# Sheet1.net
KiCad netlist of a schematic drawn in Altium Designer
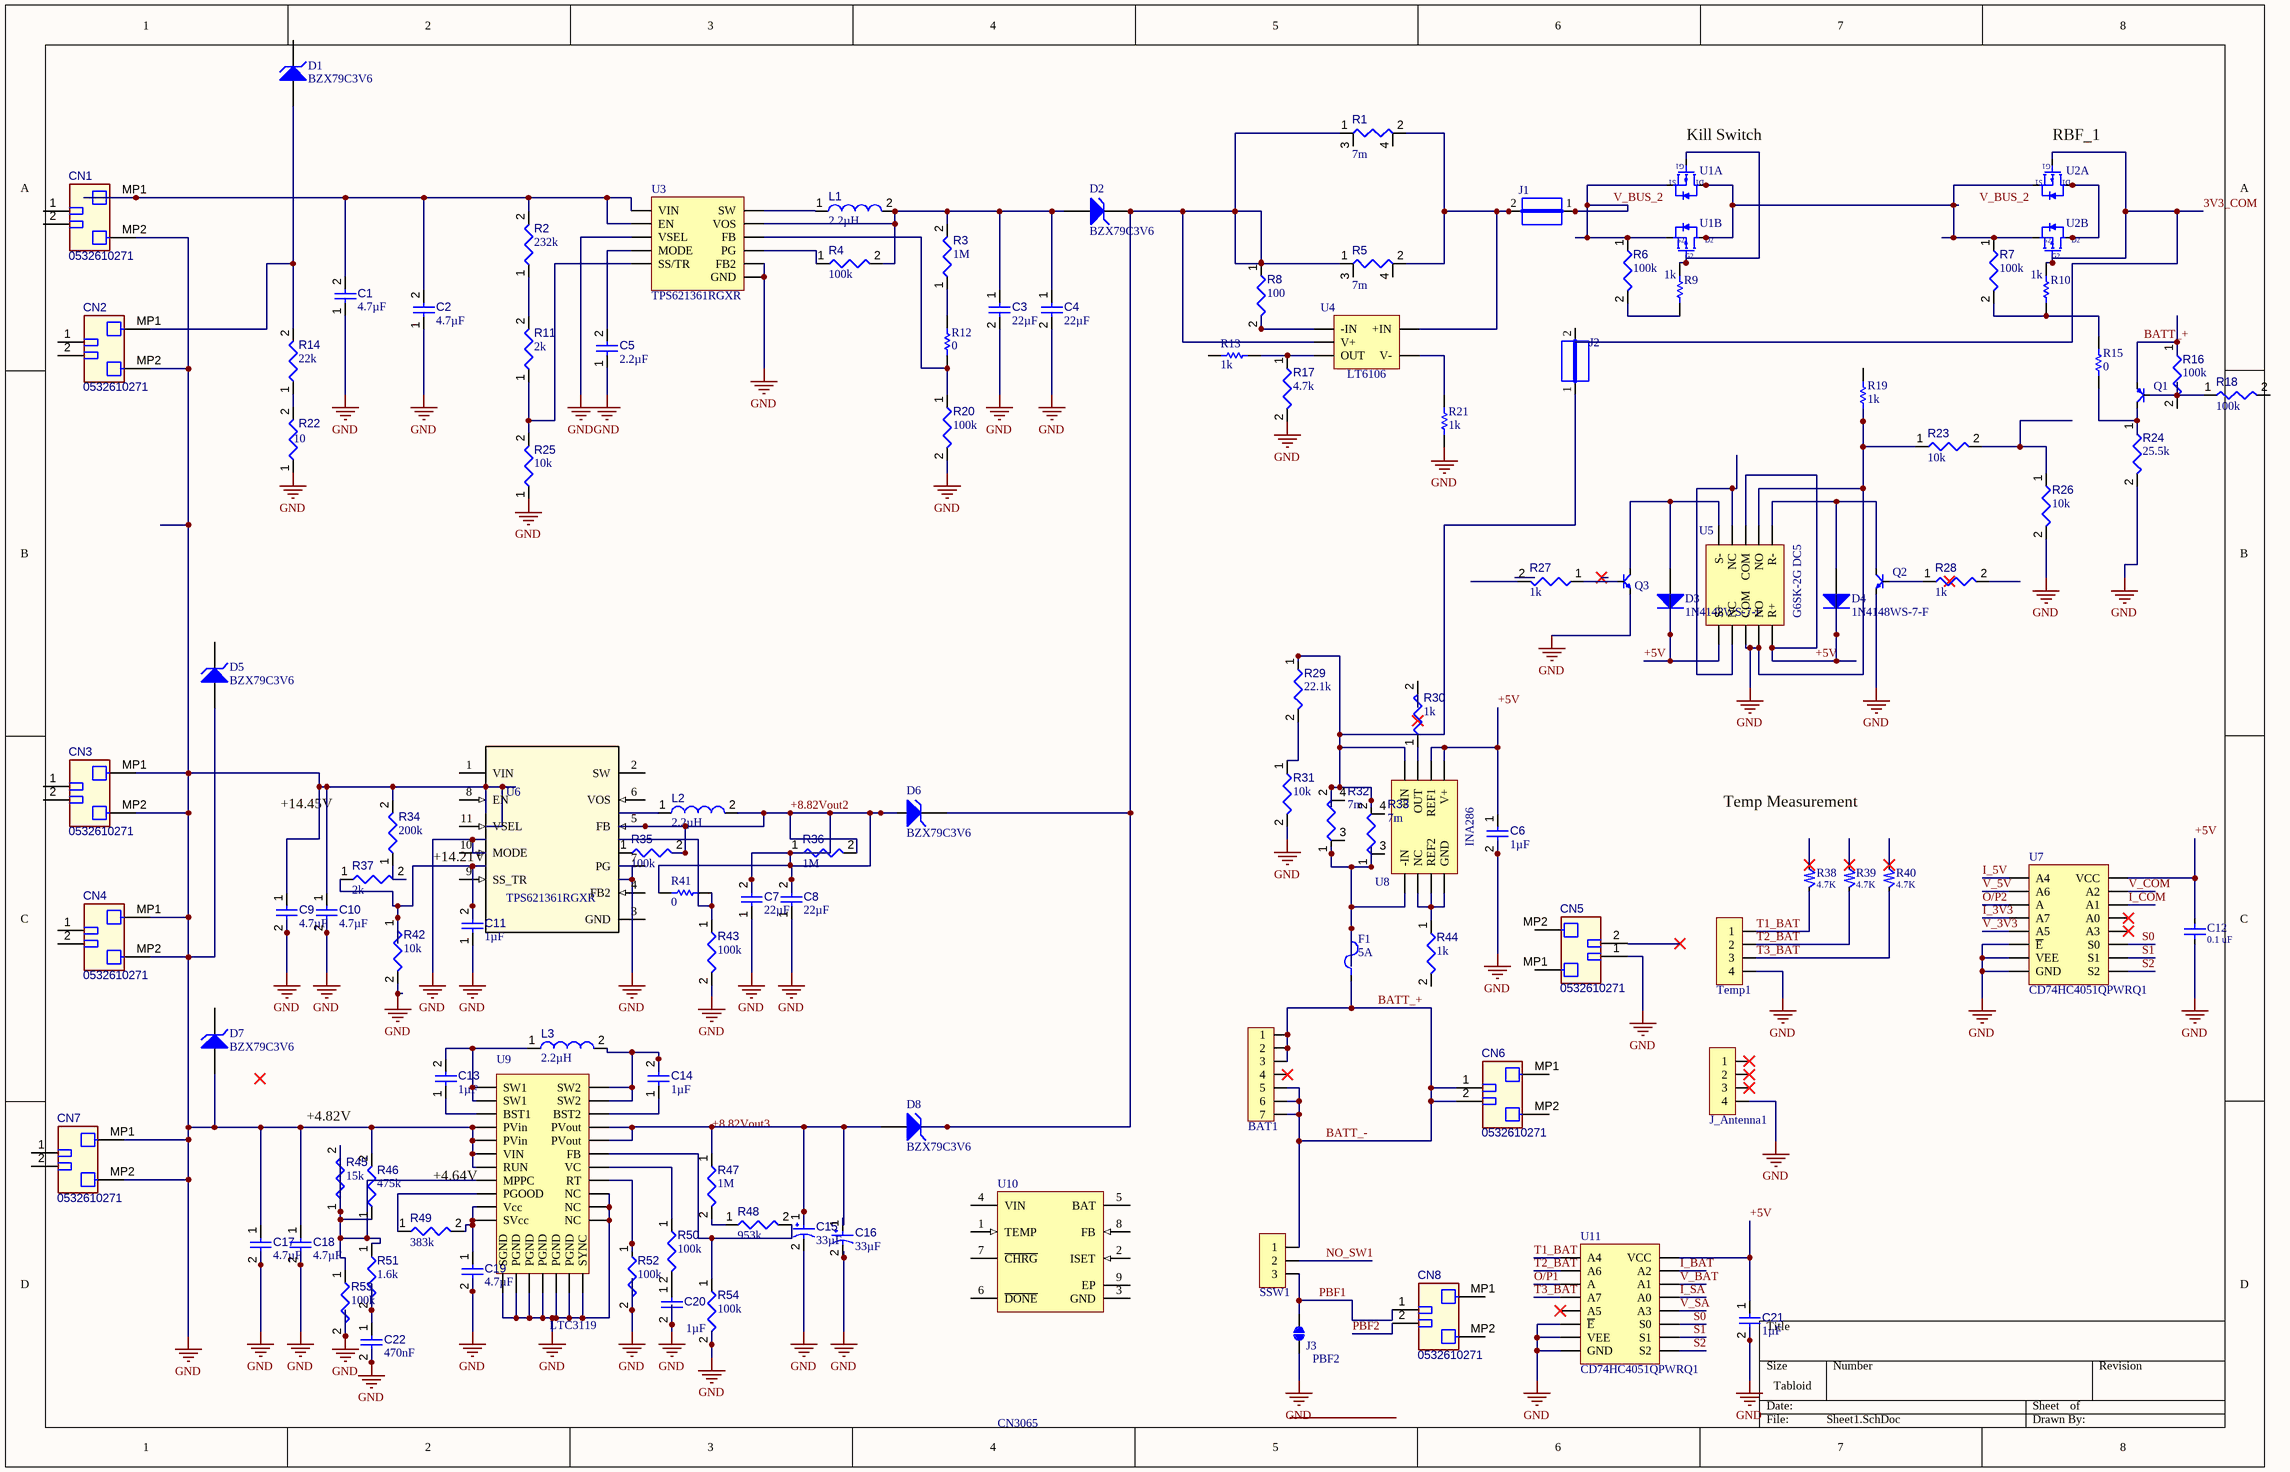
[diagram p0: Sheet1.SchDoc]

(export (version "E")
  (design (tool "Eeschema 10.0.6"))
  (components
    (comp (ref "BAT1")
      (value "53261-0771")
      (footprint "Molex_0_MFG")
      (description "CONN HEADER SMD R/A 7POS 1.25MM")
      (fields (field (name "MANUFACTURER") "Molex"))
      (libsource (lib "All_N_Cube3_Components") (part "53261-0771"))
    )
    (comp (ref "C1")
      (value "4.7µF")
      (footprint "CAPC0603(1608)100_L")
      (description "Chip Capacitor, 4.7µF +/-20%, 10V, 0603, Thickness 1 mm")
      (fields (field (name "TOLERANCE") "10%") (field (name "Comment") "Capacitor 4.7µF +/-20% 10V 0603"))
      (libsource (lib "Meshack Kinyua") (part "CAP-NP-2"))
    )
    (comp (ref "C2")
      (value "4.7µF")
      (footprint "CAPC0603(1608)100_L")
      (description "Chip Capacitor, 4.7µF +/-20%, 10V, 0603, Thickness 1 mm")
      (fields (field (name "TOLERANCE") "10%") (field (name "Comment") "Capacitor 4.7µF +/-20% 10V 0603"))
      (libsource (lib "Meshack Kinyua") (part "CAP-NP-2"))
    )
    (comp (ref "C3")
      (value "22µF")
      (footprint "CAPC0805(2012)145_L")
      (description "Chip Capacitor, 22µF +/-40%, 16V, 0805, Thickness 1.45 mm")
      (fields (field (name "TOLERANCE") "5%") (field (name "Comment") "Capacitor 22µF +/-40% 16V 0805"))
      (libsource (lib "Meshack Kinyua") (part "CAP-NP-2"))
    )
    (comp (ref "C4")
      (value "22µF")
      (footprint "CAPC0805(2012)145_L")
      (description "Chip Capacitor, 22µF +/-40%, 16V, 0805, Thickness 1.45 mm")
      (fields (field (name "TOLERANCE") "5%") (field (name "Comment") "Capacitor 22µF +/-40% 16V 0805"))
      (libsource (lib "Meshack Kinyua") (part "CAP-NP-2"))
    )
    (comp (ref "C5")
      (value "2.2µF")
      (footprint "CAPC0402(1005)60_L")
      (description "Chip Capacitor, 2,2µF +/-20%, 10V, 0402, Thickness 0.6 mm")
      (fields (field (name "TOLERANCE") "10%") (field (name "Comment") "Capacitor 2,2µF +/-20% 10V 0402"))
      (libsource (lib "Meshack Kinyua") (part "CAP-NP-2"))
    )
    (comp (ref "C6")
      (value "1µF")
      (footprint "CAPC1608X90X40LL10T20")
      (description "Chip Capacitor, 1 uF, +/- 10%, 25 V, 0603 (1608 Metric)")
      (fields (field (name "TOLERANCE") "10%") (field (name "Comment") "Capacitor 1 uF +/- 10% 25 V 0603"))
      (libsource (lib "Meshack Kinyua") (part "CAP-NP-2"))
    )
    (comp (ref "C7")
      (value "22µF")
      (footprint "CAPC0805(2012)145_L")
      (description "Chip Capacitor, 22µF +/-40%, 16V, 0805, Thickness 1.45 mm")
      (fields (field (name "TOLERANCE") "5%") (field (name "Comment") "Capacitor 22µF +/-40% 16V 0805"))
      (libsource (lib "Meshack Kinyua") (part "CAP-NP-2"))
    )
    (comp (ref "C8")
      (value "22µF")
      (footprint "CAPC0805(2012)145_L")
      (description "Chip Capacitor, 22µF +/-40%, 16V, 0805, Thickness 1.45 mm")
      (fields (field (name "TOLERANCE") "5%") (field (name "Comment") "Capacitor 22µF +/-40% 16V 0805"))
      (libsource (lib "Meshack Kinyua") (part "CAP-NP-2"))
    )
    (comp (ref "C9")
      (value "4.7µF")
      (footprint "CAPC0603(1608)100_L")
      (description "Chip Capacitor, 4.7µF +/-20%, 10V, 0603, Thickness 1 mm")
      (fields (field (name "TOLERANCE") "10%") (field (name "Comment") "Capacitor 4.7µF +/-20% 10V 0603"))
      (libsource (lib "Meshack Kinyua") (part "CAP-NP-2"))
    )
    (comp (ref "C10")
      (value "4.7µF")
      (footprint "CAPC0603(1608)100_L")
      (description "Chip Capacitor, 4.7µF +/-20%, 10V, 0603, Thickness 1 mm")
      (fields (field (name "TOLERANCE") "10%") (field (name "Comment") "Capacitor 4.7µF +/-20% 10V 0603"))
      (libsource (lib "Meshack Kinyua") (part "CAP-NP-2"))
    )
    (comp (ref "C11")
      (value "1µF")
      (footprint "CAPC1608X94X35NL15T15")
      (description "Chip Capacitor, 1 uF, +/- 10%, 16 V, 0603 (1608 Metric)")
      (fields (field (name "TOLERANCE") "10%") (field (name "Comment") "Capacitor 1 uF +/- 10% 16 V 0603"))
      (libsource (lib "Meshack Kinyua") (part "CAP-NP-2"))
    )
    (comp (ref "C12")
      (value "0.1 uF")
      (footprint "C0805C104J4RACTU")
      (description "CAP CER 0.1UF 16V X7R 0805")
      (fields
        (field (name "MANUFACTURER") "KEMET")
        (field (name "MANUFACTURER PART NUMBER") "C0805C104J4RACTU")
      )
      (libsource (lib "All_N_Cube3_Components") (part "C0805C104J4RACTU"))
    )
    (comp (ref "C13")
      (value "1µF")
      (footprint "CAPC1608X94X35NL15T15")
      (description "Chip Capacitor, 1 uF, +/- 10%, 16 V, 0603 (1608 Metric)")
      (fields (field (name "TOLERANCE") "10%") (field (name "Comment") "Capacitor 1 uF +/- 10% 16 V 0603"))
      (libsource (lib "Meshack Kinyua") (part "CAP-NP-2"))
    )
    (comp (ref "C14")
      (value "1µF")
      (footprint "CAPC1608X94X35NL15T15")
      (description "Chip Capacitor, 1 uF, +/- 10%, 16 V, 0603 (1608 Metric)")
      (fields (field (name "TOLERANCE") "10%") (field (name "Comment") "Capacitor 1 uF +/- 10% 16 V 0603"))
      (libsource (lib "Meshack Kinyua") (part "CAP-NP-2"))
    )
    (comp (ref "C15")
      (value "33µF")
      (footprint "EEF-CX1E330R-Footprint-1")
      (description "Aluminum Organic Polymer Capacitors 33uF 25volt SP-Cap AEC-Q200")
      (fields (field (name "TOLERANCE") "20%") (field (name "Comment") "Capacitor 33µF +/-20% 25V 2917"))
      (libsource (lib "Meshack Kinyua") (part "CAP-P-2"))
    )
    (comp (ref "C16")
      (value "33µF")
      (footprint "EEF-CX1E330R-Footprint-1")
      (description "Aluminum Organic Polymer Capacitors 33uF 25volt SP-Cap AEC-Q200")
      (fields (field (name "TOLERANCE") "20%") (field (name "Comment") "Capacitor 33µF +/-20% 25V 2917"))
      (libsource (lib "Meshack Kinyua") (part "CAP-P-2"))
    )
    (comp (ref "C17")
      (value "4.7µF")
      (footprint "CAPC0603(1608)100_L")
      (description "Chip Capacitor, 4.7µF +/-20%, 10V, 0603, Thickness 1 mm")
      (fields (field (name "TOLERANCE") "10%") (field (name "Comment") "Capacitor 4.7µF +/-20% 10V 0603"))
      (libsource (lib "Meshack Kinyua") (part "CAP-NP-2"))
    )
    (comp (ref "C18")
      (value "4.7µF")
      (footprint "CAPC0603(1608)100_L")
      (description "Chip Capacitor, 4.7µF +/-20%, 10V, 0603, Thickness 1 mm")
      (fields (field (name "TOLERANCE") "10%") (field (name "Comment") "Capacitor 4.7µF +/-20% 10V 0603"))
      (libsource (lib "Meshack Kinyua") (part "CAP-NP-2"))
    )
    (comp (ref "C19")
      (value "4.7µF")
      (footprint "CAPC0603(1608)100_L")
      (description "Chip Capacitor, 4.7µF +/-20%, 10V, 0603, Thickness 1 mm")
      (fields (field (name "TOLERANCE") "10%") (field (name "Comment") "Capacitor 4.7µF +/-20% 10V 0603"))
      (libsource (lib "Meshack Kinyua") (part "CAP-NP-2"))
    )
    (comp (ref "C20")
      (value "1µF")
      (footprint "CAPC1005X55X25LL05T10")
      (description "Chip Capacitor, 1 uF, +/- 10%, 6.3 V, 0402 (1005 Metric)")
      (fields (field (name "TOLERANCE") "10%") (field (name "Comment") "Capacitor 1 uF +/- 10% 6.3 V 0402"))
      (libsource (lib "Meshack Kinyua") (part "CAP-NP-2"))
    )
    (comp (ref "C21")
      (value "1µF")
      (footprint "CAPC1608X94X35NL15T15")
      (description "Chip Capacitor, 1 uF, +/- 10%, 16 V, 0603 (1608 Metric)")
      (fields (field (name "TOLERANCE") "10%") (field (name "Comment") "Capacitor 1 uF +/- 10% 16 V 0603"))
      (libsource (lib "Meshack Kinyua") (part "CAP-NP-2"))
    )
    (comp (ref "C22")
      (value "470nF")
      (footprint "CAPC0402(1005)60_L")
      (description "Chip Capacitor, 470nF +/-40%, 10V, 0402, Thickness 0.6 mm")
      (fields (field (name "TOLERANCE") "20%") (field (name "Comment") "Capacitor 470nF +/-40% 10V 0402"))
      (libsource (lib "Meshack Kinyua") (part "CAP-NP-2"))
    )
    (comp (ref "CN1")
      (value "0532610271")
      (footprint "MOLX-532610271_V")
      (description "Header, Pitch 1.25 mm, 1 x 2 Position, Height 3.6 mm, -40 to 85 degC")
      (libsource (lib "Meshack Kinyua") (part "CMP-00144-3"))
    )
    (comp (ref "CN2")
      (value "0532610271")
      (footprint "MOLX-532610271_V")
      (description "Header, Pitch 1.25 mm, 1 x 2 Position, Height 3.6 mm, -40 to 85 degC")
      (libsource (lib "Meshack Kinyua") (part "CMP-00144-3"))
    )
    (comp (ref "CN3")
      (value "0532610271")
      (footprint "MOLX-532610271_V")
      (description "Header, Pitch 1.25 mm, 1 x 2 Position, Height 3.6 mm, -40 to 85 degC")
      (libsource (lib "Meshack Kinyua") (part "CMP-00144-3"))
    )
    (comp (ref "CN4")
      (value "0532610271")
      (footprint "MOLX-532610271_V")
      (description "Header, Pitch 1.25 mm, 1 x 2 Position, Height 3.6 mm, -40 to 85 degC")
      (libsource (lib "Meshack Kinyua") (part "CMP-00144-3"))
    )
    (comp (ref "CN5")
      (value "0532610271")
      (footprint "MOLX-532610271_V")
      (description "Header, Pitch 1.25 mm, 1 x 2 Position, Height 3.6 mm, -40 to 85 degC")
      (libsource (lib "") (part "CMP-00144-3_1"))
    )
    (comp (ref "CN6")
      (value "0532610271")
      (footprint "MOLX-532610271_V")
      (description "Header, Pitch 1.25 mm, 1 x 2 Position, Height 3.6 mm, -40 to 85 degC")
      (libsource (lib "Meshack Kinyua") (part "CMP-00144-3"))
    )
    (comp (ref "CN7")
      (value "0532610271")
      (footprint "MOLX-532610271_V")
      (description "Header, Pitch 1.25 mm, 1 x 2 Position, Height 3.6 mm, -40 to 85 degC")
      (libsource (lib "Meshack Kinyua") (part "CMP-00144-3"))
    )
    (comp (ref "CN8")
      (value "0532610271")
      (footprint "MOLX-532610271_V")
      (description "Header, Pitch 1.25 mm, 1 x 2 Position, Height 3.6 mm, -40 to 85 degC")
      (libsource (lib "Meshack Kinyua") (part "CMP-00144-3"))
    )
    (comp (ref "D1")
      (value "BZX79C3V6")
      (footprint "FAIR-DO-35-2")
      (description "Zener Diode, 3.6 V, 5 mA, -65 to 200 degC, 2-Pin DO-35, RoHS, Bulk")
      (fields (field (name "MANUFACTURER") "Fairchild Semiconductor") (field (name "TOLERANCE") "6%"))
      (libsource (lib "Meshack Kinyua") (part "DZEN-AK-2"))
    )
    (comp (ref "D2")
      (value "BZX79C3V6")
      (footprint "FAIR-DO-35-2")
      (description "Zener Diode, 3.6 V, 5 mA, -65 to 200 degC, 2-Pin DO-35, RoHS, Bulk")
      (fields (field (name "MANUFACTURER") "Fairchild Semiconductor") (field (name "TOLERANCE") "6%"))
      (libsource (lib "Meshack Kinyua") (part "DZEN-AK-2"))
    )
    (comp (ref "D3")
      (value "1N4148WS-7-F")
      (footprint "DIOD-SOD323-2-A_V")
      (description "Fast Switching Diode, 75 V, 0.3 A, -65 to 150 degC, 2-Pin SOD323, RoHS, Tape and Reel")
      (fields (field (name "MANUFACTURER") "Diodes Inc"))
      (libsource (lib "Meshack Kinyua") (part "D-AK-2"))
    )
    (comp (ref "D4")
      (value "1N4148WS-7-F")
      (footprint "DIOD-SOD323-2-A_V")
      (description "Fast Switching Diode, 75 V, 0.3 A, -65 to 150 degC, 2-Pin SOD323, RoHS, Tape and Reel")
      (fields (field (name "MANUFACTURER") "Diodes Inc"))
      (libsource (lib "Meshack Kinyua") (part "D-AK-2"))
    )
    (comp (ref "D5")
      (value "BZX79C3V6")
      (footprint "FAIR-DO-35-2")
      (description "Zener Diode, 3.6 V, 5 mA, -65 to 200 degC, 2-Pin DO-35, RoHS, Bulk")
      (fields (field (name "MANUFACTURER") "Fairchild Semiconductor") (field (name "TOLERANCE") "6%"))
      (libsource (lib "Meshack Kinyua") (part "DZEN-AK-2"))
    )
    (comp (ref "D6")
      (value "BZX79C3V6")
      (footprint "FAIR-DO-35-2")
      (description "Zener Diode, 3.6 V, 5 mA, -65 to 200 degC, 2-Pin DO-35, RoHS, Bulk")
      (fields (field (name "MANUFACTURER") "Fairchild Semiconductor") (field (name "TOLERANCE") "6%"))
      (libsource (lib "Meshack Kinyua") (part "DZEN-AK-2"))
    )
    (comp (ref "D7")
      (value "BZX79C3V6")
      (footprint "FAIR-DO-35-2")
      (description "Zener Diode, 3.6 V, 5 mA, -65 to 200 degC, 2-Pin DO-35, RoHS, Bulk")
      (fields (field (name "MANUFACTURER") "Fairchild Semiconductor") (field (name "TOLERANCE") "6%"))
      (libsource (lib "Meshack Kinyua") (part "DZEN-AK-2"))
    )
    (comp (ref "D8")
      (value "BZX79C3V6")
      (footprint "FAIR-DO-35-2")
      (description "Zener Diode, 3.6 V, 5 mA, -65 to 200 degC, 2-Pin DO-35, RoHS, Bulk")
      (fields (field (name "MANUFACTURER") "Fairchild Semiconductor") (field (name "TOLERANCE") "6%"))
      (libsource (lib "Meshack Kinyua") (part "DZEN-AK-2"))
    )
    (comp (ref "F1")
      (value "1206L500/12SLPR")
      (footprint "1206L500/12SLPR")
      (description "PTC RESET FUSE 5.0A 12V 1206")
      (fields (field (name "MANUFACTURER") "Littelfuse") (field (name "TRIP CURRENT") "5A"))
      (libsource (lib "All_N_Cube3_Components") (part "1206L500/12SLPR"))
    )
    (comp (ref "J1") (value "JUMPER") (footprint "JUMPER") (libsource (lib "Meshack Kinyua") (part "JUMPER")))
    (comp (ref "J2") (value "JUMPER") (footprint "JUMPER") (libsource (lib "") (part "JUMPER_1")))
    (comp (ref "J3")
      (value "JUMPER")
      (footprint "JUMPER")
      (description "OPTION SELECTION 2POS PAD")
      (libsource (lib "RG_Projects") (part "JUMPER"))
    )
    (comp (ref "J_Antenna1")
      (value "53261-0471")
      (footprint "53261-0471")
      (description "CONN HEADER SMD R/A 4POS 1.25MM")
      (fields (field (name "MANUFACTURER") "Molex"))
      (libsource (lib "RG_Projects") (part "53261-0471"))
    )
    (comp (ref "L1")
      (value "2.2µH")
      (footprint "IND1005X55X20VL5T10")
      (description "Chip Inductor, 2.2 nH, +/- 0.3 nH, 400 mA, -40 to 85 degC, 0402 (1005 Metric), RoHS, Tape and Reel")
      (fields (field (name "MANUFACTURER") "Panasonic") (field (name "TOLERANCE") "5%"))
      (libsource (lib "Meshack Kinyua") (part "IND-2"))
    )
    (comp (ref "L2")
      (value "2.2µH")
      (footprint "IND1005X55X20VL5T10")
      (description "Chip Inductor, 2.2 nH, +/- 0.3 nH, 400 mA, -40 to 85 degC, 0402 (1005 Metric), RoHS, Tape and Reel")
      (fields (field (name "MANUFACTURER") "Panasonic") (field (name "TOLERANCE") "5%"))
      (libsource (lib "Meshack Kinyua") (part "IND-2"))
    )
    (comp (ref "L3")
      (value "2.2µH")
      (footprint "IND1005X55X20VL5T10")
      (description "Chip Inductor, 2.2 nH, +/- 0.3 nH, 400 mA, -40 to 85 degC, 0402 (1005 Metric), RoHS, Tape and Reel")
      (fields (field (name "MANUFACTURER") "Panasonic") (field (name "TOLERANCE") "5%"))
      (libsource (lib "Meshack Kinyua") (part "IND-2"))
    )
    (comp (ref "Q1")
      (value "CMPT404A TR")
      (footprint "CMPT404A TR")
      (description "Bipolar Transistors - BJT PNP Silicon Chopper SMT Transistor")
      (fields (field (name "MANUFACTURER") "Central Semiconductor"))
      (libsource (lib "All_N_Cube3_Components") (part "CMPT404A TR"))
    )
    (comp (ref "Q2")
      (value "SMMBT3904LT3G")
      (footprint "SMMBT3904LT3G")
      (description "TRANS NPN 40V 0.2A SOT23")
      (fields (field (name "MANUFACTURER") "ON Semiconductor"))
      (libsource (lib "All_N_Cube3_Components") (part "SMMBT3904LT3G"))
    )
    (comp (ref "Q3")
      (value "SMMBT3904LT3G")
      (footprint "SMMBT3904LT3G")
      (description "TRANS NPN 40V 0.2A SOT23")
      (fields (field (name "MANUFACTURER") "ON Semiconductor"))
      (libsource (lib "All_N_Cube3_Components") (part "SMMBT3904LT3G"))
    )
    (comp (ref "R1")
      (value "7m")
      (footprint "SUSUMU-3216T4A")
      (description "Chip Resistor, 0,007 Ohms, +/-1%, 63 mW, -55 to 155 degC, 1206")
      (fields (field (name "TOLERANCE") "1%") (field (name "Comment") "Resistor 7mR +/-1% 1206 63 mW"))
      (libsource (lib "Meshack Kinyua") (part "RES-4"))
    )
    (comp (ref "R2")
      (value "232k")
      (footprint "RESC0402(1005)_L")
      (description "Chip Resistor, 232 kOhms, +/-1 %, 63 mW, -55 to 155 degC, 0402")
      (fields (field (name "POWER") "63mW") (field (name "TOLERANCE") "1%"))
      (libsource (lib "Meshack Kinyua") (part "RES-2"))
    )
    (comp (ref "R3")
      (value "1M")
      (footprint "RESC0402(1005)_L")
      (description "Chip Resistor, 1 MOhms, +/-5 %, 63 mW, -55 to 155 degC, 0402")
      (fields (field (name "POWER") "63mW") (field (name "TOLERANCE") "5%"))
      (libsource (lib "Meshack Kinyua") (part "RES-2"))
    )
    (comp (ref "R4")
      (value "100k")
      (footprint "RESC3216X60X45ML15T20")
      (description "Chip Resistor, 100 KOhm, +/- 1%, 0.25 W, -55 to 155 degC, 1206 (3216 Metric)")
      (fields (field (name "TOLERANCE") "1%") (field (name "POWER") "250mW"))
      (libsource (lib "Meshack Kinyua") (part "RES-2"))
    )
    (comp (ref "R5")
      (value "7m")
      (footprint "SUSUMU-3216T4A")
      (description "Chip Resistor, 0,007 Ohms, +/-1%, 63 mW, -55 to 155 degC, 1206")
      (fields (field (name "TOLERANCE") "1%") (field (name "Comment") "Resistor 7mR +/-1% 1206 63 mW"))
      (libsource (lib "Meshack Kinyua") (part "RES-4"))
    )
    (comp (ref "R6")
      (value "100k")
      (footprint "RESC1608X55X25ML10T15")
      (description "Chip Resistor, 100 KOhm, +/- 1%, 0.1 W, -55 to 155 degC, 0603 (1608 Metric)")
      (fields (field (name "TOLERANCE") "1%") (field (name "POWER") "100mW"))
      (libsource (lib "Meshack Kinyua") (part "RES-2"))
    )
    (comp (ref "R7")
      (value "100k")
      (footprint "RESC1608X55X25ML10T15")
      (description "Chip Resistor, 100 KOhm, +/- 1%, 0.1 W, -55 to 155 degC, 0603 (1608 Metric)")
      (fields (field (name "TOLERANCE") "1%") (field (name "POWER") "100mW"))
      (libsource (lib "Meshack Kinyua") (part "RES-2"))
    )
    (comp (ref "R8")
      (value "100")
      (footprint "RESA60-630X240")
      (description "Axial Resistor, 100 Ohm, +/- 1%, 0.25 W, -55 to 155 degC, 2-Pin THD, RoHS, Bulk")
      (fields (field (name "MANUFACTURER") "Yageo") (field (name "TOLERANCE") "1%"))
      (libsource (lib "Meshack Kinyua") (part "RES-2"))
    )
    (comp (ref "R9")
      (value "1k")
      (footprint "RESC3116X70X50ML13T20")
      (description "Chip Resistor, 1 KOhm, +/- 1%, 0.25 W, -55 to 155 degC, 1206 (3216 Metric)")
      (fields (field (name "TOLERANCE") "1%") (field (name "POWER") "250mW"))
      (libsource (lib "") (part "RES-2_1"))
    )
    (comp (ref "R10")
      (value "1k")
      (footprint "RESC3116X70X50ML13T20")
      (description "Chip Resistor, 1 KOhm, +/- 1%, 0.25 W, -55 to 155 degC, 1206 (3216 Metric)")
      (fields (field (name "TOLERANCE") "1%") (field (name "POWER") "250mW"))
      (libsource (lib "") (part "RES-2_1"))
    )
    (comp (ref "R11")
      (value "2k")
      (footprint "RESC0402(1005)_L")
      (description "Chip Resistor, 2 kOhms, +/-5 %, 63 mW, -55 to 155 degC, 0402")
      (fields (field (name "TOLERANCE") "5%") (field (name "POWER") "63mW"))
      (libsource (lib "Meshack Kinyua") (part "RES-2"))
    )
    (comp (ref "R12")
      (value "0")
      (footprint "RESC1608X55X25ML10T15")
      (description "Chip Resistor, 0 Ohm, 0.1 W, -55 to 155 degC, 0603 (1608 Metric)")
      (fields (field (name "POWER") "100mW") (field (name "TOLERANCE") "5%"))
      (libsource (lib "") (part "RES-2_1"))
    )
    (comp (ref "R13")
      (value "1k")
      (footprint "RESC2013X70X40ML20T20")
      (description "Chip Resistor, 1 KOhm, +/- 1%, 0.125 W, -55 to 155 degC, 0805 (2013 Metric)")
      (fields (field (name "TOLERANCE") "1%") (field (name "POWER") "125mW"))
      (libsource (lib "") (part "RES-2_1"))
    )
    (comp (ref "R14")
      (value "22k")
      (footprint "RESC0402(1005)_L")
      (description "Chip Resistor, 22 kOhms, +/-1 %, 63 mW, -55 to 155 degC, 0402")
      (fields (field (name "POWER") "63mW") (field (name "TOLERANCE") "1%"))
      (libsource (lib "Meshack Kinyua") (part "RES-2"))
    )
    (comp (ref "R15")
      (value "0")
      (footprint "RESC1608X55X25ML10T15")
      (description "Chip Resistor, 0 Ohm, 0.1 W, -55 to 155 degC, 0603 (1608 Metric)")
      (fields (field (name "POWER") "100mW") (field (name "TOLERANCE") "5%"))
      (libsource (lib "") (part "RES-2_1"))
    )
    (comp (ref "R16")
      (value "100k")
      (footprint "RESC0402(1005)_L")
      (description "Chip Resistor, 100 kOhms, +/-1 %, 63 mW, -55 to 155 degC, 0402")
      (fields (field (name "TOLERANCE") "1%") (field (name "POWER") "63mW"))
      (libsource (lib "Meshack Kinyua") (part "RES-2"))
    )
    (comp (ref "R17")
      (value "4.7k")
      (footprint "RESC3116X70X50ML13T20")
      (description "Chip Resistor, 4.7 KOhm, +/- 1%, 0.25 W, -55 to 155 degC, 1206 (3216 Metric)")
      (fields (field (name "POWER") "250mW") (field (name "TOLERANCE") "1%"))
      (libsource (lib "Meshack Kinyua") (part "RES-2"))
    )
    (comp (ref "R18")
      (value "100k")
      (footprint "RESC1005X40X25ML05T05")
      (description "Chip Resistor, 1 KOhm, +/- 1%, 63 mW, -55 to 155 degC, 0402 (1005 Metric)")
      (fields (field (name "POWER") "63mW") (field (name "TOLERANCE") "1%"))
      (libsource (lib "Meshack Kinyua") (part "RES-2"))
    )
    (comp (ref "R19")
      (value "1k")
      (footprint "RESC1005X40X25ML05T05")
      (description "Chip Resistor, 1 KOhm, +/- 1%, 0.1 W, -55 to 155 degC, 0402 (1005 Metric)")
      (fields (field (name "POWER") "100mW") (field (name "TOLERANCE") "1%"))
      (libsource (lib "") (part "RES-2_1"))
    )
    (comp (ref "R20")
      (value "100k")
      (footprint "RESC1608X55X25ML10T15")
      (description "Chip Resistor, 100 KOhm, +/- 1%, 0.1 W, -55 to 155 degC, 0603 (1608 Metric)")
      (fields (field (name "TOLERANCE") "1%") (field (name "POWER") "100mW"))
      (libsource (lib "Meshack Kinyua") (part "RES-2"))
    )
    (comp (ref "R21")
      (value "1k")
      (footprint "RESC2013X70X40ML20T20")
      (description "Chip Resistor, 1 KOhm, +/- 1%, 0.125 W, -55 to 155 degC, 0805 (2013 Metric)")
      (fields (field (name "TOLERANCE") "1%") (field (name "POWER") "125mW"))
      (libsource (lib "") (part "RES-2_1"))
    )
    (comp (ref "R22")
      (value "10")
      (footprint "RESC1005X40X25ML10T10")
      (description "Chip Resistor, 10 Ohm, +/- 5%, 0.063 W, -55 to 155 degC, 0402 (1005 Metric)")
      (fields (field (name "POWER") "63mW") (field (name "TOLERANCE") "5%"))
      (libsource (lib "Meshack Kinyua") (part "RES-2"))
    )
    (comp (ref "R23")
      (value "10k")
      (footprint "RESA60-630X240")
      (description "Axial Resistor, 10 KOhm, +/- 1%, 0.25 W, -55 to 155 degC, 2-Pin THD, RoHS, Bulk")
      (fields (field (name "TOLERANCE") "1%") (field (name "POWER") "250mW"))
      (libsource (lib "Meshack Kinyua") (part "RES-2"))
    )
    (comp (ref "R24")
      (value "25.5k")
      (footprint "RESC0402(1005)_L")
      (description "Chip Resistor, 25,5 kOhms, +/-1 %, 63 mW, -55 to 155 degC, 0402")
      (fields (field (name "TOLERANCE") "1%") (field (name "POWER") "63mW"))
      (libsource (lib "Meshack Kinyua") (part "RES-2"))
    )
    (comp (ref "R25")
      (value "10k")
      (footprint "RESC1608X55X25ML10T15")
      (description "Chip Resistor, 10 KOhm, +/- 1%, 01 W, -55 to 155 degC, 0603 (1608 Metric)")
      (fields (field (name "POWER") "100mW") (field (name "TOLERANCE") "1%"))
      (libsource (lib "Meshack Kinyua") (part "RES-2"))
    )
    (comp (ref "R26")
      (value "10k")
      (footprint "RESA60-630X240")
      (description "Axial Resistor, 10 KOhm, +/- 1%, 0.25 W, -55 to 155 degC, 2-Pin THD, RoHS, Bulk")
      (fields (field (name "TOLERANCE") "1%") (field (name "POWER") "250mW"))
      (libsource (lib "Meshack Kinyua") (part "RES-2"))
    )
    (comp (ref "R27")
      (value "1k")
      (footprint "RESC0805(2012)_L")
      (description "Chip Resistor, 1 kOhms, +/-5%, 125 mW, -55 to 155 degC, 0805")
      (fields (field (name "TOLERANCE") "5%") (field (name "POWER") "125mW"))
      (libsource (lib "Meshack Kinyua") (part "RES-2"))
    )
    (comp (ref "R28")
      (value "1k")
      (footprint "RESC0805(2012)_L")
      (description "Chip Resistor, 1 kOhms, +/-5%, 125 mW, -55 to 155 degC, 0805")
      (fields (field (name "TOLERANCE") "5%") (field (name "POWER") "125mW"))
      (libsource (lib "Meshack Kinyua") (part "RES-2"))
    )
    (comp (ref "R29")
      (value "22.1k")
      (footprint "RESA60-630X240")
      (description "Axial Resistor, 22.1 KOhm, +/- 1%, 0.25 W, -55 to 155 degC, 2-Pin THD, RoHS, Bulk")
      (fields (field (name "TOLERANCE") "1%") (field (name "POWER") "250mW"))
      (libsource (lib "Meshack Kinyua") (part "RES-2"))
    )
    (comp (ref "R30")
      (value "1k")
      (footprint "RESC0805(2012)_L")
      (description "Chip Resistor, 1 kOhms, +/-5%, 125 mW, -55 to 155 degC, 0805")
      (fields (field (name "TOLERANCE") "5%") (field (name "POWER") "125mW"))
      (libsource (lib "Meshack Kinyua") (part "RES-2"))
    )
    (comp (ref "R31")
      (value "10k")
      (footprint "RESC2013X50X35ML15T15")
      (description "Chip Resistor, 10 KOhm, +/- 1%, 125 mW, -55 to 155 degC, 0805 (2012 Metric)")
      (fields (field (name "TOLERANCE") "1%") (field (name "POWER") "125mW"))
      (libsource (lib "Meshack Kinyua") (part "RES-2"))
    )
    (comp (ref "R32")
      (value "7m")
      (footprint "SUSUMU-3216T4A")
      (description "Chip Resistor, 0,007 Ohms, +/-1%, 63 mW, -55 to 155 degC, 1206")
      (fields (field (name "TOLERANCE") "1%") (field (name "Comment") "Resistor 7mR +/-1% 1206 63 mW"))
      (libsource (lib "Meshack Kinyua") (part "RES-4"))
    )
    (comp (ref "R33")
      (value "7m")
      (footprint "SUSUMU-3216T4A")
      (description "Chip Resistor, 0,007 Ohms, +/-1%, 63 mW, -55 to 155 degC, 1206")
      (fields (field (name "TOLERANCE") "1%") (field (name "Comment") "Resistor 7mR +/-1% 1206 63 mW"))
      (libsource (lib "Meshack Kinyua") (part "RES-4"))
    )
    (comp (ref "R34")
      (value "200k")
      (footprint "RESC0402(1005)_L")
      (description "Chip Resistor, 200 kOhms, +/-1 %, 63 mW, -55 to 155 degC, 0402")
      (fields (field (name "POWER") "63mW") (field (name "TOLERANCE") "1%"))
      (libsource (lib "Meshack Kinyua") (part "RES-2"))
    )
    (comp (ref "R35")
      (value "100k")
      (footprint "RESC1608X55X25ML10T15")
      (description "Chip Resistor, 100 KOhm, +/- 1%, 0.1 W, -55 to 155 degC, 0603 (1608 Metric)")
      (fields (field (name "TOLERANCE") "1%") (field (name "POWER") "100mW"))
      (libsource (lib "Meshack Kinyua") (part "RES-2"))
    )
    (comp (ref "R36")
      (value "1M")
      (footprint "RESC0402(1005)_L")
      (description "Chip Resistor, 1 MOhms, +/-1 %, 63 mW, -55 to 155 degC, 0402")
      (fields (field (name "TOLERANCE") "1%") (field (name "POWER") "63mW"))
      (libsource (lib "Meshack Kinyua") (part "RES-2"))
    )
    (comp (ref "R37")
      (value "2k")
      (footprint "RESC0402(1005)_L")
      (description "Chip Resistor, 2 kOhms, +/-5 %, 63 mW, -55 to 155 degC, 0402")
      (fields (field (name "TOLERANCE") "5%") (field (name "POWER") "63mW"))
      (libsource (lib "Meshack Kinyua") (part "RES-2"))
    )
    (comp (ref "R38")
      (value "4.7K")
      (footprint "RG_Projects:ERJ-P06F4701V")
      (description "RES 4.7K OHM 1% 1/2W 0805")
      (fields
        (field (name "MANUFACTURER") "Panasonic Electronic Components")
        (field (name "MANUFACTURER PART NUMBER") "ERJ-P06F4701V")
      )
      (libsource (lib "All_N_Cube3_Components") (part "ERJ-P06F4701V"))
    )
    (comp (ref "R39")
      (value "4.7K")
      (footprint "RG_Projects:ERJ-P06F4701V")
      (description "RES 4.7K OHM 1% 1/2W 0805")
      (fields
        (field (name "MANUFACTURER") "Panasonic Electronic Components")
        (field (name "MANUFACTURER PART NUMBER") "ERJ-P06F4701V")
      )
      (libsource (lib "All_N_Cube3_Components") (part "ERJ-P06F4701V"))
    )
    (comp (ref "R40")
      (value "4.7K")
      (footprint "RG_Projects:ERJ-P06F4701V")
      (description "RES 4.7K OHM 1% 1/2W 0805")
      (fields
        (field (name "MANUFACTURER") "Panasonic Electronic Components")
        (field (name "MANUFACTURER PART NUMBER") "ERJ-P06F4701V")
      )
      (libsource (lib "All_N_Cube3_Components") (part "ERJ-P06F4701V"))
    )
    (comp (ref "R41")
      (value "0")
      (footprint "RESC3116X70X50ML13T20")
      (description "Chip Resistor, 0 Ohm, 0.25 W, -55 to 155 degC, 1206 (3216 Metric)")
      (fields (field (name "TOLERANCE") "0.05%") (field (name "POWER") "250mW"))
      (libsource (lib "") (part "RES-2_1"))
    )
    (comp (ref "R42")
      (value "10k")
      (footprint "RESC1608X55X25ML10T15")
      (description "Chip Resistor, 10 KOhm, +/- 1%, 01 W, -55 to 155 degC, 0603 (1608 Metric)")
      (fields (field (name "POWER") "100mW") (field (name "TOLERANCE") "1%"))
      (libsource (lib "Meshack Kinyua") (part "RES-2"))
    )
    (comp (ref "R43")
      (value "100k")
      (footprint "RESC1608X55X25ML10T15")
      (description "Chip Resistor, 100 KOhm, +/- 1%, 0.1 W, -55 to 155 degC, 0603 (1608 Metric)")
      (fields (field (name "TOLERANCE") "1%") (field (name "POWER") "100mW"))
      (libsource (lib "Meshack Kinyua") (part "RES-2"))
    )
    (comp (ref "R44")
      (value "1k")
      (footprint "RESC0805(2012)_L")
      (description "Chip Resistor, 1 kOhms, +/-5%, 125 mW, -55 to 155 degC, 0805")
      (fields (field (name "TOLERANCE") "5%") (field (name "POWER") "125mW"))
      (libsource (lib "Meshack Kinyua") (part "RES-2"))
    )
    (comp (ref "R45")
      (value "15k")
      (footprint "RESC1005X40X25ML10T10")
      (description "Chip Resistor, 15 KOhm, +/- 1%, 0.063 W, -55 to 155 degC, 0402 (1005 Metric)")
      (fields (field (name "POWER") "63mW") (field (name "TOLERANCE") "1%"))
      (libsource (lib "Meshack Kinyua") (part "RES-2"))
    )
    (comp (ref "R46")
      (value "475k")
      (footprint "RESA60-630X240")
      (description "Axial Resistor, 475 KOhm, +/- 1%, 0.25 W, -55 to 155 degC, 2-Pin THD, RoHS, Bulk")
      (fields (field (name "POWER") "250mW") (field (name "TOLERANCE") "1%"))
      (libsource (lib "Meshack Kinyua") (part "RES-2"))
    )
    (comp (ref "R47")
      (value "1M")
      (footprint "RESA60-630X240")
      (description "Axial Resistor, 1 MOhm, +/- 1%, 250 mW, -55 to 155 degC, 2-Pin THD, RoHS, Bulk")
      (fields (field (name "MANUFACTURER") "Yageo") (field (name "TOLERANCE") "1%"))
      (libsource (lib "Meshack Kinyua") (part "RES-2"))
    )
    (comp (ref "R48")
      (value "953k")
      (footprint "RESC0402(1005)_L")
      (description "953K 0.063W 1% 0402 (1005 Metric)  SMD")
      (fields (field (name "POWER") "63mW") (field (name "TOLERANCE") "1%"))
      (libsource (lib "Meshack Kinyua") (part "Res"))
    )
    (comp (ref "R49")
      (value "383k")
      (footprint "RESC0402(1005)_L")
      (description "Chip Resistor, 383 kOhms, +/-1 %, 63 mW, -55 to 155 degC, 0402")
      (fields (field (name "TOLERANCE") "1%") (field (name "POWER") "63mW"))
      (libsource (lib "Meshack Kinyua") (part "RES-2"))
    )
    (comp (ref "R50")
      (value "100k")
      (footprint "RESC1005X40X25ML05T05")
      (description "Chip Resistor, 100 KOhm, +/- 1%, 0.063 W, -55 to 155 degC, 0402 (1005 Metric)")
      (fields (field (name "TOLERANCE") "1%") (field (name "POWER") "63mW"))
      (libsource (lib "Meshack Kinyua") (part "RES-2"))
    )
    (comp (ref "R51")
      (value "1.6k")
      (footprint "RESC0402(1005)_L")
      (description "1K6 0.063W 5% 0402 (1005 Metric)  SMD")
      (fields (field (name "TOLERANCE") "5%") (field (name "POWER") "63mW"))
      (libsource (lib "Meshack Kinyua") (part "1D6KR2J"))
    )
    (comp (ref "R52")
      (value "100k")
      (footprint "RESC1005X40X25ML05T05")
      (description "Chip Resistor, 100 KOhm, +/- 1%, 0.063 W, -55 to 155 degC, 0402 (1005 Metric)")
      (fields (field (name "TOLERANCE") "1%") (field (name "POWER") "63mW"))
      (libsource (lib "Meshack Kinyua") (part "RES-2"))
    )
    (comp (ref "R53")
      (value "100k")
      (footprint "RESC0402(1005)_L")
      (description "100K 0.063W 1% 0402 (1005 Metric)  SMD")
      (fields (field (name "POWER") "63mW") (field (name "TOLERANCE") "1%"))
      (libsource (lib "Meshack Kinyua") (part "100KR2F"))
    )
    (comp (ref "R54")
      (value "100k")
      (footprint "RESC3216X60X45ML15T20")
      (description "Chip Resistor, 100 KOhm, +/- 1%, 0.25 W, -55 to 155 degC, 1206 (3216 Metric)")
      (fields (field (name "TOLERANCE") "1%") (field (name "POWER") "250mW"))
      (libsource (lib "Meshack Kinyua") (part "RES-2"))
    )
    (comp (ref "SSW1")
      (value "53261-0371")
      (footprint "53261-0371")
      (description "CONN HEADER SMD R/A 3POS 1.25MM")
      (fields (field (name "MANUFACTURER") "Molex"))
      (libsource (lib "All_N_Cube3_Components") (part "53261-0371"))
    )
    (comp (ref "Temp1")
      (value "53261-0471")
      (footprint "53261-0471")
      (description "CONN HEADER SMD R/A 4POS 1.25MM")
      (fields (field (name "MANUFACTURER") "Molex"))
      (libsource (lib "All_N_Cube3_Components") (part "53261-0471"))
    )
    (comp (ref "U1")
      (value "IRF7329TRPBF")
      (footprint "Infineon_PG-DSO-8_MFG")
      (description "MOSFET 2P-CH 12V 9.2A 8-SOIC")
      (fields (field (name "MANUFACTURER") "International Rectifier"))
      (libsource (lib "RG_Projects") (part "IRF7329TRPBF"))
    )
    (comp (ref "U2")
      (value "IRF7329TRPBF")
      (footprint "Infineon_PG-DSO-8_MFG")
      (description "MOSFET 2P-CH 12V 9.2A 8-SOIC")
      (fields (field (name "MANUFACTURER") "International Rectifier"))
      (libsource (lib "RG_Projects") (part "IRF7329TRPBF"))
    )
    (comp (ref "U3")
      (value "TPS621361RGXR")
      (footprint "RGX0011A")
      (description "IC REG BUCK ADJUSTABLE 4A 11VQFN")
      (fields (field (name "MANUFACTURER") "Texas Instruments"))
      (libsource (lib "RG_Projects") (part "TPS621361RGXR"))
    )
    (comp (ref "U4")
      (value "LT6106")
      (footprint "LT6106HS5#TRPBF")
      (description "IC OPAMP CURR SENSE TSOT23-5")
      (fields
        (field (name "MANUFACTURER") "Linear Technology")
        (field (name "MANUFACTURER PART NUMBER") "LT6106HS5#TRMPBF")
      )
      (libsource (lib "All_N_Cube3_Components") (part "LT6106HS5#TRPBF"))
    )
    (comp (ref "U5")
      (value "G6SK-2G DC5")
      (footprint "Omron_0_MFG")
      (description "RELAY TELECOM DPDT 2A 5V")
      (fields (field (name "MANUFACTURER") "Omron Electronics Inc-EMC Div"))
      (libsource (lib "All_N_Cube3_Components") (part "G6SK-2G DC5"))
    )
    (comp (ref "U6")
      (value "TPS621361RGXR")
      (footprint "RGX0011A")
      (description "No Description Available")
      (fields (field (name "COPYRIGHT") "Copyright (C) 2022 Ultra Librarian. All rights reserved."))
      (libsource (lib "TPS621361RGXR") (part "TPS621361RGXR"))
    )
    (comp (ref "U7")
      (value "CD74HC4051QPWRQ1")
      (footprint "PW16")
      (description "IC MUX/DEMUX 8X1 16TSSOP")
      (fields (field (name "MANUFACTURER") "Texas Instruments") (field (name "BASE PART NUMBER") "74HC4051"))
      (libsource (lib "All_N_Cube3_Components") (part "CD74HC4051QPWRQ1"))
    )
    (comp (ref "U8")
      (value "INA286")
      (footprint "D8_TEX")
      (description "IC CURRENT SHUNT MONITOR 8SOIC")
      (fields
        (field (name "MANUFACTURER") "Texas Instruments")
        (field (name "MANUFACTURER PART NUMBER") "INA286AQDRQ1")
      )
      (libsource (lib "RG_Projects") (part "INA286AQDRQ1"))
    )
    (comp (ref "U9")
      (value "LTC3119")
      (footprint "FE_24_ADI")
      (description "IC REG BCK BST ADJ 5A 28QFN")
      (fields
        (field (name "MANUFACTURER") "Analog Devices / Linear Technology")
        (field (name "MANUFACTURER PART NUMBER") "LTC3119EUFD#PBF")
      )
      (libsource (lib "SSQ-132-02-T-D") (part "LTC3119EUFD#PBF"))
    )
    (comp (ref "U10")
      (value "CN3065")
      (footprint "CONS-DFN-8_M")
      (fields (field (name "MANUFACTURER") "Consonance Electronic"))
      (libsource (lib "Meshack Kinyua") (part "CONS-CN3065-DFN-8"))
    )
    (comp (ref "U11")
      (value "CD74HC4051QPWRQ1")
      (footprint "PW16")
      (description "IC MUX/DEMUX 8X1 16TSSOP")
      (fields (field (name "MANUFACTURER") "Texas Instruments") (field (name "BASE PART NUMBER") "74HC4051"))
      (libsource (lib "All_N_Cube3_Components") (part "CD74HC4051QPWRQ1"))
    )
  )
  (nets
    (net (code "1") (name "/+5V") (class "Default")
      (node (ref "C12") (pin "2") (pinfunction "2_2") (pintype "passive"))
      (node (ref "C21") (pin "1") (pinfunction "1_1") (pintype "passive"))
      (node (ref "C6") (pin "1") (pinfunction "1_1") (pintype "passive"))
      (node (ref "D3") (pin "2") (pinfunction "K_2") (pintype "passive"))
      (node (ref "D4") (pin "2") (pinfunction "K_2") (pintype "passive"))
      (node (ref "U11") (pin "16") (pinfunction "VCC_16") (pintype "passive"))
      (node (ref "U5") (pin "1") (pinfunction "S+_1") (pintype "passive"))
      (node (ref "U5") (pin "5") (pinfunction "R+_5") (pintype "passive"))
      (node (ref "U5") (pin "8") (pinfunction "COM_8") (pintype "passive"))
      (node (ref "U7") (pin "16") (pinfunction "VCC_16") (pintype "passive"))
      (node (ref "U8") (pin "6") (pinfunction "V+_6") (pintype "passive"))
      (node (ref "U8") (pin "7") (pinfunction "REF1_7") (pintype "passive"))
    )
    (net (code "2") (name "/+8.82Vout2") (class "Default")
      (node (ref "C7") (pin "2") (pinfunction "2_2") (pintype "passive"))
      (node (ref "C8") (pin "2") (pinfunction "2_2") (pintype "passive"))
      (node (ref "D6") (pin "1") (pinfunction "A_1") (pintype "passive"))
      (node (ref "L2") (pin "2") (pinfunction "2_2") (pintype "passive"))
      (node (ref "R35") (pin "2") (pinfunction "2_2") (pintype "passive"))
      (node (ref "R36") (pin "1") (pinfunction "1_1") (pintype "passive"))
      (node (ref "R36") (pin "2") (pinfunction "2_2") (pintype "passive"))
      (node (ref "R41") (pin "1") (pinfunction "1_1") (pintype "passive"))
      (node (ref "U6") (pin "5") (pinfunction "FB_5") (pintype "input"))
    )
    (net (code "3") (name "/+8.82Vout3") (class "Default")
      (node (ref "C15") (pin "1") (pinfunction "1_1") (pintype "passive"))
      (node (ref "C16") (pin "1") (pinfunction "1_1") (pintype "passive"))
      (node (ref "D8") (pin "1") (pinfunction "A_1") (pintype "passive"))
      (node (ref "R47") (pin "1") (pinfunction "1_1") (pintype "passive"))
      (node (ref "U9") (pin "3") (pinfunction "PVout_3") (pintype "passive"))
      (node (ref "U9") (pin "4") (pinfunction "PVout_4") (pintype "passive"))
    )
    (net (code "4") (name "/3V3_COM") (class "Default")
      (node (ref "R10") (pin "2") (pinfunction "2_2") (pintype "passive"))
      (node (ref "U2") (pin "2") (pinfunction "G1_2") (pintype "passive"))
      (node (ref "U2") (pin "4") (pinfunction "G2_4") (pintype "passive"))
    )
    (net (code "5") (name "/BATT_+") (class "Default")
      (node (ref "BAT1") (pin "1") (pinfunction "1_1") (pintype "passive"))
      (node (ref "BAT1") (pin "2") (pinfunction "2_2") (pintype "passive"))
      (node (ref "BAT1") (pin "3") (pinfunction "3_3") (pintype "passive"))
      (node (ref "BAT1") (pin "5") (pinfunction "5_5") (pintype "passive"))
      (node (ref "BAT1") (pin "6") (pinfunction "6_6") (pintype "passive"))
      (node (ref "BAT1") (pin "7") (pinfunction "7_7") (pintype "passive"))
      (node (ref "CN6") (pin "1") (pinfunction "1_1") (pintype "passive"))
      (node (ref "CN6") (pin "2") (pinfunction "2_2") (pintype "passive"))
      (node (ref "F1") (pin "1") (pinfunction "1_1") (pintype "passive"))
      (node (ref "Q1") (pin "3") (pinfunction "C_3") (pintype "passive"))
      (node (ref "R16") (pin "1") (pinfunction "1_1") (pintype "passive"))
      (node (ref "SSW1") (pin "1") (pinfunction "1_1") (pintype "passive"))
    )
    (net (code "6") (name "/I_3V3") (class "Default")
      (node (ref "U7") (pin "4") (pinfunction "A7_4") (pintype "passive"))
    )
    (net (code "7") (name "/I_5V") (class "Default")
      (node (ref "U7") (pin "1") (pinfunction "A4_1") (pintype "passive"))
    )
    (net (code "8") (name "/I_BAT") (class "Default")
      (node (ref "U11") (pin "15") (pinfunction "A2_15") (pintype "passive"))
    )
    (net (code "9") (name "/I_COM") (class "Default")
      (node (ref "U7") (pin "14") (pinfunction "A1_14") (pintype "passive"))
    )
    (net (code "10") (name "/I_SA") (class "Default")
      (node (ref "U11") (pin "13") (pinfunction "A0_13") (pintype "passive"))
    )
    (net (code "11") (name "/NO_SW1") (class "Default")
      (node (ref "SSW1") (pin "2") (pinfunction "2_2") (pintype "passive"))
    )
    (net (code "12") (name "/O{slash}P1") (class "Default")
      (node (ref "U11") (pin "3") (pinfunction "A_3") (pintype "passive"))
    )
    (net (code "13") (name "/O{slash}P2") (class "Default")
      (node (ref "U7") (pin "3") (pinfunction "A_3") (pintype "passive"))
    )
    (net (code "14") (name "/PBF1") (class "Default")
      (node (ref "CN8") (pin "1") (pinfunction "1_1") (pintype "passive"))
      (node (ref "J3") (pin "2") (pinfunction "2_2") (pintype "passive"))
      (node (ref "SSW1") (pin "3") (pinfunction "3_3") (pintype "passive"))
    )
    (net (code "15") (name "/PBF2") (class "Default")
      (node (ref "CN8") (pin "2") (pinfunction "2_2") (pintype "passive"))
    )
    (net (code "16") (name "/S0") (class "Default")
      (node (ref "U11") (pin "11") (pinfunction "S0_11") (pintype "passive"))
      (node (ref "U7") (pin "11") (pinfunction "S0_11") (pintype "passive"))
    )
    (net (code "17") (name "/S1") (class "Default")
      (node (ref "U11") (pin "10") (pinfunction "S1_10") (pintype "passive"))
      (node (ref "U7") (pin "10") (pinfunction "S1_10") (pintype "passive"))
    )
    (net (code "18") (name "/S2") (class "Default")
      (node (ref "U11") (pin "9") (pinfunction "S2_9") (pintype "passive"))
      (node (ref "U7") (pin "9") (pinfunction "S2_9") (pintype "passive"))
    )
    (net (code "19") (name "/T1_BAT") (class "Default")
      (node (ref "R38") (pin "1") (pinfunction "1_1") (pintype "passive"))
      (node (ref "Temp1") (pin "1") (pinfunction "1_1") (pintype "passive"))
      (node (ref "U11") (pin "1") (pinfunction "A4_1") (pintype "passive"))
    )
    (net (code "20") (name "/T2_BAT") (class "Default")
      (node (ref "R39") (pin "1") (pinfunction "1_1") (pintype "passive"))
      (node (ref "Temp1") (pin "2") (pinfunction "2_2") (pintype "passive"))
      (node (ref "U11") (pin "2") (pinfunction "A6_2") (pintype "passive"))
    )
    (net (code "21") (name "/T3_BAT") (class "Default")
      (node (ref "R40") (pin "1") (pinfunction "1_1") (pintype "passive"))
      (node (ref "Temp1") (pin "3") (pinfunction "3_3") (pintype "passive"))
      (node (ref "U11") (pin "4") (pinfunction "A7_4") (pintype "passive"))
    )
    (net (code "22") (name "/V_3V3") (class "Default")
      (node (ref "U7") (pin "5") (pinfunction "A5_5") (pintype "passive"))
    )
    (net (code "23") (name "/V_5V") (class "Default")
      (node (ref "U7") (pin "2") (pinfunction "A6_2") (pintype "passive"))
    )
    (net (code "24") (name "/V_BAT") (class "Default")
      (node (ref "U11") (pin "14") (pinfunction "A1_14") (pintype "passive"))
    )
    (net (code "25") (name "/V_BUS_2") (class "Default")
      (node (ref "J1") (pin "1") (pinfunction "1_1") (pintype "passive"))
      (node (ref "R6") (pin "1") (pinfunction "1_1") (pintype "passive"))
      (node (ref "U1") (pin "1") (pinfunction "S1_1") (pintype "passive"))
      (node (ref "U1") (pin "3") (pinfunction "S2_3") (pintype "passive"))
    )
    (net (code "26") (name "/V_COM") (class "Default")
      (node (ref "U7") (pin "15") (pinfunction "A2_15") (pintype "passive"))
    )
    (net (code "27") (name "/V_SA") (class "Default")
      (node (ref "U11") (pin "12") (pinfunction "A3_12") (pintype "passive"))
    )
    (net (code "28") (name "GND") (class "Default")
      (node (ref "C1") (pin "1") (pinfunction "1_1") (pintype "passive"))
      (node (ref "C10") (pin "1") (pinfunction "1_1") (pintype "passive"))
      (node (ref "C10") (pin "2") (pinfunction "2_2") (pintype "passive"))
      (node (ref "C11") (pin "1") (pinfunction "1_1") (pintype "passive"))
      (node (ref "C12") (pin "1") (pinfunction "1_1") (pintype "passive"))
      (node (ref "C15") (pin "2") (pinfunction "2_2") (pintype "passive"))
      (node (ref "C16") (pin "2") (pinfunction "2_2") (pintype "passive"))
      (node (ref "C17") (pin "1") (pinfunction "1_1") (pintype "passive"))
      (node (ref "C17") (pin "2") (pinfunction "2_2") (pintype "passive"))
      (node (ref "C18") (pin "1") (pinfunction "1_1") (pintype "passive"))
      (node (ref "C18") (pin "2") (pinfunction "2_2") (pintype "passive"))
      (node (ref "C19") (pin "2") (pinfunction "2_2") (pintype "passive"))
      (node (ref "C2") (pin "1") (pinfunction "1_1") (pintype "passive"))
      (node (ref "C20") (pin "2") (pinfunction "2_2") (pintype "passive"))
      (node (ref "C21") (pin "2") (pinfunction "2_2") (pintype "passive"))
      (node (ref "C22") (pin "2") (pinfunction "2_2") (pintype "passive"))
      (node (ref "C3") (pin "2") (pinfunction "2_2") (pintype "passive"))
      (node (ref "C4") (pin "2") (pinfunction "2_2") (pintype "passive"))
      (node (ref "C5") (pin "1") (pinfunction "1_1") (pintype "passive"))
      (node (ref "C6") (pin "2") (pinfunction "2_2") (pintype "passive"))
      (node (ref "C7") (pin "1") (pinfunction "1_1") (pintype "passive"))
      (node (ref "C8") (pin "1") (pinfunction "1_1") (pintype "passive"))
      (node (ref "C9") (pin "1") (pinfunction "1_1") (pintype "passive"))
      (node (ref "C9") (pin "2") (pinfunction "2_2") (pintype "passive"))
      (node (ref "CN1") (pin "MP2") (pinfunction "MP2_MP2") (pintype "passive"))
      (node (ref "CN2") (pin "MP2") (pinfunction "MP2_MP2") (pintype "passive"))
      (node (ref "CN3") (pin "MP1") (pinfunction "MP1_MP1") (pintype "passive"))
      (node (ref "CN3") (pin "MP2") (pinfunction "MP2_MP2") (pintype "passive"))
      (node (ref "CN4") (pin "MP1") (pinfunction "MP1_MP1") (pintype "passive"))
      (node (ref "CN4") (pin "MP2") (pinfunction "MP2_MP2") (pintype "passive"))
      (node (ref "CN5") (pin "1") (pinfunction "1_1") (pintype "passive"))
      (node (ref "CN7") (pin "MP1") (pinfunction "MP1_MP1") (pintype "passive"))
      (node (ref "CN7") (pin "MP2") (pinfunction "MP2_MP2") (pintype "passive"))
      (node (ref "D5") (pin "1") (pinfunction "A_1") (pintype "passive"))
      (node (ref "D7") (pin "1") (pinfunction "A_1") (pintype "passive"))
      (node (ref "J3") (pin "1") (pinfunction "1_1") (pintype "passive"))
      (node (ref "J_Antenna1") (pin "4") (pinfunction "4_4") (pintype "passive"))
      (node (ref "Q2") (pin "2") (pinfunction "E_2") (pintype "passive"))
      (node (ref "Q3") (pin "2") (pinfunction "E_2") (pintype "passive"))
      (node (ref "R17") (pin "2") (pinfunction "2_2") (pintype "passive"))
      (node (ref "R19") (pin "1") (pinfunction "1_1") (pintype "passive"))
      (node (ref "R20") (pin "2") (pinfunction "2_2") (pintype "passive"))
      (node (ref "R21") (pin "1") (pinfunction "1_1") (pintype "passive"))
      (node (ref "R22") (pin "1") (pinfunction "1_1") (pintype "passive"))
      (node (ref "R23") (pin "1") (pinfunction "1_1") (pintype "passive"))
      (node (ref "R24") (pin "2") (pinfunction "2_2") (pintype "passive"))
      (node (ref "R25") (pin "1") (pinfunction "1_1") (pintype "passive"))
      (node (ref "R26") (pin "2") (pinfunction "2_2") (pintype "passive"))
      (node (ref "R31") (pin "2") (pinfunction "2_2") (pintype "passive"))
      (node (ref "R34") (pin "2") (pinfunction "2_2") (pintype "passive"))
      (node (ref "R42") (pin "2") (pinfunction "2_2") (pintype "passive"))
      (node (ref "R43") (pin "2") (pinfunction "2_2") (pintype "passive"))
      (node (ref "R46") (pin "2") (pinfunction "2_2") (pintype "passive"))
      (node (ref "R52") (pin "2") (pinfunction "2_2") (pintype "passive"))
      (node (ref "R53") (pin "2") (pinfunction "2_2") (pintype "passive"))
      (node (ref "R54") (pin "2") (pinfunction "2_2") (pintype "passive"))
      (node (ref "Temp1") (pin "4") (pinfunction "4_4") (pintype "passive"))
      (node (ref "U11") (pin "6") (pinfunction "~{E}_6") (pintype "passive"))
      (node (ref "U11") (pin "7") (pinfunction "VEE_7") (pintype "passive"))
      (node (ref "U11") (pin "8") (pinfunction "GND_8") (pintype "passive"))
      (node (ref "U3") (pin "11") (pinfunction "VSEL_11") (pintype "passive"))
      (node (ref "U3") (pin "3") (pinfunction "GND_3") (pintype "passive"))
      (node (ref "U3") (pin "4") (pinfunction "FB2_4") (pintype "passive"))
      (node (ref "U5") (pin "3") (pinfunction "COM_3") (pintype "passive"))
      (node (ref "U5") (pin "4") (pinfunction "NO_4") (pintype "passive"))
      (node (ref "U5") (pin "7") (pinfunction "NO_7") (pintype "passive"))
      (node (ref "U7") (pin "6") (pinfunction "~{E}_6") (pintype "passive"))
      (node (ref "U7") (pin "7") (pinfunction "VEE_7") (pintype "passive"))
      (node (ref "U7") (pin "8") (pinfunction "GND_8") (pintype "passive"))
      (node (ref "U9") (pin "1") (pinfunction "PGND_1") (pintype "passive"))
      (node (ref "U9") (pin "11") (pinfunction "SGND_11") (pintype "passive"))
      (node (ref "U9") (pin "15") (pinfunction "RUN_15") (pintype "passive"))
      (node (ref "U9") (pin "16") (pinfunction "VIN_16") (pintype "passive"))
      (node (ref "U9") (pin "17") (pinfunction "PGND_17") (pintype "passive"))
      (node (ref "U9") (pin "19") (pinfunction "PVin_19") (pintype "passive"))
      (node (ref "U9") (pin "20") (pinfunction "PVin_20") (pintype "passive"))
      (node (ref "U9") (pin "22") (pinfunction "PGND_22") (pintype "passive"))
      (node (ref "U9") (pin "24") (pinfunction "NC_24") (pintype "passive"))
      (node (ref "U9") (pin "25") (pinfunction "SYNC_25") (pintype "passive"))
      (node (ref "U9") (pin "26") (pinfunction "NC_26") (pintype "passive"))
      (node (ref "U9") (pin "27") (pinfunction "NC_27") (pintype "passive"))
      (node (ref "U9") (pin "29") (pinfunction "PGND_29") (pintype "passive"))
      (node (ref "U9") (pin "6") (pinfunction "PGND_6") (pintype "passive"))
    )
    (net (code "29") (name "Net-(C11-Pad2)") (class "Default")
      (node (ref "C11") (pin "2") (pinfunction "2_2") (pintype "passive"))
      (node (ref "R37") (pin "1") (pinfunction "1_1") (pintype "passive"))
      (node (ref "R42") (pin "1") (pinfunction "1_1") (pintype "passive"))
    )
    (net (code "30") (name "Net-(C13-Pad2)") (class "Default")
      (node (ref "C13") (pin "2") (pinfunction "2_2") (pintype "passive"))
      (node (ref "L3") (pin "1") (pinfunction "1_1") (pintype "passive"))
      (node (ref "U9") (pin "18") (pinfunction "SW1_18") (pintype "passive"))
      (node (ref "U9") (pin "21") (pinfunction "SW1_21") (pintype "passive"))
    )
    (net (code "31") (name "Net-(C14-Pad2)") (class "Default")
      (node (ref "C14") (pin "2") (pinfunction "2_2") (pintype "passive"))
      (node (ref "L3") (pin "2") (pinfunction "2_2") (pintype "passive"))
      (node (ref "U9") (pin "2") (pinfunction "SW2_2") (pintype "passive"))
      (node (ref "U9") (pin "5") (pinfunction "SW2_5") (pintype "passive"))
    )
    (net (code "32") (name "Net-(C20-Pad1)") (class "Default")
      (node (ref "C20") (pin "1") (pinfunction "1_1") (pintype "passive"))
      (node (ref "R50") (pin "2") (pinfunction "2_2") (pintype "passive"))
    )
    (net (code "33") (name "Net-(C22-Pad1)") (class "Default")
      (node (ref "C22") (pin "1") (pinfunction "1_1") (pintype "passive"))
      (node (ref "R51") (pin "2") (pinfunction "2_2") (pintype "passive"))
    )
    (net (code "34") (name "Net-(D1-A)") (class "Default")
      (node (ref "CN2") (pin "MP1") (pinfunction "MP1_MP1") (pintype "passive"))
      (node (ref "D1") (pin "1") (pinfunction "A_1") (pintype "passive"))
      (node (ref "R14") (pin "2") (pinfunction "2_2") (pintype "passive"))
    )
    (net (code "35") (name "Net-(D2-A)") (class "Default")
      (node (ref "C3") (pin "1") (pinfunction "1_1") (pintype "passive"))
      (node (ref "C4") (pin "1") (pinfunction "1_1") (pintype "passive"))
      (node (ref "D2") (pin "1") (pinfunction "A_1") (pintype "passive"))
      (node (ref "L1") (pin "2") (pinfunction "2_2") (pintype "passive"))
      (node (ref "R3") (pin "2") (pinfunction "2_2") (pintype "passive"))
      (node (ref "R4") (pin "2") (pinfunction "2_2") (pintype "passive"))
      (node (ref "U3") (pin "6") (pinfunction "VOS_6") (pintype "passive"))
    )
    (net (code "36") (name "Net-(D2-K)") (class "Default")
      (node (ref "D2") (pin "2") (pinfunction "K_2") (pintype "passive"))
      (node (ref "D6") (pin "2") (pinfunction "K_2") (pintype "passive"))
      (node (ref "D8") (pin "2") (pinfunction "K_2") (pintype "passive"))
      (node (ref "R1") (pin "1") (pinfunction "I1_1") (pintype "passive"))
      (node (ref "R5") (pin "1") (pinfunction "I1_1") (pintype "passive"))
      (node (ref "R8") (pin "1") (pinfunction "1_1") (pintype "passive"))
      (node (ref "U4") (pin "5") (pinfunction "V+_5") (pintype "passive"))
    )
    (net (code "37") (name "Net-(D3-A)") (class "Default")
      (node (ref "D3") (pin "1") (pinfunction "A_1") (pintype "passive"))
      (node (ref "Q3") (pin "3") (pinfunction "C_3") (pintype "passive"))
      (node (ref "U5") (pin "10") (pinfunction "S-_10") (pintype "passive"))
    )
    (net (code "38") (name "Net-(D4-A)") (class "Default")
      (node (ref "D4") (pin "1") (pinfunction "A_1") (pintype "passive"))
      (node (ref "Q2") (pin "3") (pinfunction "C_3") (pintype "passive"))
      (node (ref "U5") (pin "6") (pinfunction "R-_6") (pintype "passive"))
    )
    (net (code "39") (name "Net-(Q1-B)") (class "Default")
      (node (ref "Q1") (pin "1") (pinfunction "B_1") (pintype "passive"))
      (node (ref "R18") (pin "1") (pinfunction "1_1") (pintype "passive"))
    )
    (net (code "40") (name "Net-(Q1-E)") (class "Default")
      (node (ref "Q1") (pin "2") (pinfunction "E_2") (pintype "passive"))
      (node (ref "R15") (pin "1") (pinfunction "1_1") (pintype "passive"))
      (node (ref "R24") (pin "1") (pinfunction "1_1") (pintype "passive"))
    )
    (net (code "41") (name "Net-(Q2-B)") (class "Default")
      (node (ref "Q2") (pin "1") (pinfunction "B_1") (pintype "passive"))
      (node (ref "R28") (pin "1") (pinfunction "1_1") (pintype "passive"))
    )
    (net (code "42") (name "Net-(Q3-B)") (class "Default")
      (node (ref "Q3") (pin "1") (pinfunction "B_1") (pintype "passive"))
      (node (ref "R27") (pin "1") (pinfunction "1_1") (pintype "passive"))
    )
    (net (code "43") (name "Net-(R1-I2)") (class "Default")
      (node (ref "J1") (pin "2") (pinfunction "2_2") (pintype "passive"))
      (node (ref "R1") (pin "2") (pinfunction "I2_2") (pintype "passive"))
      (node (ref "R5") (pin "2") (pinfunction "I2_2") (pintype "passive"))
      (node (ref "U4") (pin "4") (pinfunction "+IN_4") (pintype "passive"))
    )
    (net (code "44") (name "Net-(R6-Pad2)") (class "Default")
      (node (ref "R6") (pin "2") (pinfunction "2_2") (pintype "passive"))
      (node (ref "R9") (pin "1") (pinfunction "1_1") (pintype "passive"))
    )
    (net (code "45") (name "Net-(R10-Pad1)") (class "Default")
      (node (ref "R10") (pin "1") (pinfunction "1_1") (pintype "passive"))
      (node (ref "R15") (pin "2") (pinfunction "2_2") (pintype "passive"))
      (node (ref "R7") (pin "2") (pinfunction "2_2") (pintype "passive"))
    )
    (net (code "46") (name "Net-(R11-Pad2)") (class "Default")
      (node (ref "R11") (pin "2") (pinfunction "2_2") (pintype "passive"))
      (node (ref "R2") (pin "1") (pinfunction "1_1") (pintype "passive"))
    )
    (net (code "47") (name "Net-(R12-Pad2)") (class "Default")
      (node (ref "R12") (pin "2") (pinfunction "2_2") (pintype "passive"))
      (node (ref "R3") (pin "1") (pinfunction "1_1") (pintype "passive"))
    )
    (net (code "48") (name "Net-(R14-Pad1)") (class "Default")
      (node (ref "R14") (pin "1") (pinfunction "1_1") (pintype "passive"))
      (node (ref "R22") (pin "2") (pinfunction "2_2") (pintype "passive"))
    )
    (net (code "49") (name "Net-(R23-Pad2)") (class "Default")
      (node (ref "R23") (pin "2") (pinfunction "2_2") (pintype "passive"))
      (node (ref "R26") (pin "1") (pinfunction "1_1") (pintype "passive"))
    )
    (net (code "50") (name "Net-(R29-Pad2)") (class "Default")
      (node (ref "R29") (pin "2") (pinfunction "2_2") (pintype "passive"))
      (node (ref "R31") (pin "1") (pinfunction "1_1") (pintype "passive"))
    )
    (net (code "51") (name "Net-(R32-I1)") (class "Default")
      (node (ref "F1") (pin "2") (pinfunction "2_2") (pintype "passive"))
      (node (ref "R32") (pin "1") (pinfunction "I1_1") (pintype "passive"))
      (node (ref "R33") (pin "1") (pinfunction "I1_1") (pintype "passive"))
      (node (ref "U8") (pin "1") (pinfunction "-IN_1") (pintype "passive"))
    )
    (net (code "52") (name "Net-(R32-I2)") (class "Default")
      (node (ref "J2") (pin "1") (pinfunction "1_1") (pintype "passive"))
      (node (ref "R29") (pin "1") (pinfunction "1_1") (pintype "passive"))
      (node (ref "R32") (pin "2") (pinfunction "I2_2") (pintype "passive"))
      (node (ref "R33") (pin "2") (pinfunction "I2_2") (pintype "passive"))
      (node (ref "U8") (pin "8") (pinfunction "+IN_8") (pintype "passive"))
    )
    (net (code "53") (name "Net-(R34-Pad1)") (class "Default")
      (node (ref "R34") (pin "1") (pinfunction "1_1") (pintype "passive"))
      (node (ref "R37") (pin "2") (pinfunction "2_2") (pintype "passive"))
    )
    (net (code "54") (name "Net-(R41-Pad2)") (class "Default")
      (node (ref "R41") (pin "2") (pinfunction "2_2") (pintype "passive"))
      (node (ref "R43") (pin "1") (pinfunction "1_1") (pintype "passive"))
    )
    (net (code "55") (name "Net-(R47-Pad2)") (class "Default")
      (node (ref "R47") (pin "2") (pinfunction "2_2") (pintype "passive"))
      (node (ref "R48") (pin "1") (pinfunction "1_1") (pintype "passive"))
    )
    (net (code "56") (name "Net-(U1A-G1)") (class "Default")
      (node (ref "R9") (pin "2") (pinfunction "2_2") (pintype "passive"))
      (node (ref "U1") (pin "2") (pinfunction "G1_2") (pintype "passive"))
      (node (ref "U1") (pin "4") (pinfunction "G2_4") (pintype "passive"))
    )
    (net (code "57") (name "Net-(U2A-D1-Pad7)") (class "Default")
      (node (ref "U2") (pin "5") (pinfunction "D2_5") (pintype "passive"))
      (node (ref "U2") (pin "6") (pinfunction "D2_6") (pintype "passive"))
      (node (ref "U2") (pin "7") (pinfunction "D1_7") (pintype "passive"))
      (node (ref "U2") (pin "8") (pinfunction "D1_8") (pintype "passive"))
    )
    (net (code "58") (name "Net-(U2A-S1)") (class "Default")
      (node (ref "R7") (pin "1") (pinfunction "1_1") (pintype "passive"))
      (node (ref "U1") (pin "5") (pinfunction "D2_5") (pintype "passive"))
      (node (ref "U1") (pin "6") (pinfunction "D2_6") (pintype "passive"))
      (node (ref "U1") (pin "7") (pinfunction "D1_7") (pintype "passive"))
      (node (ref "U1") (pin "8") (pinfunction "D1_8") (pintype "passive"))
      (node (ref "U2") (pin "1") (pinfunction "S1_1") (pintype "passive"))
      (node (ref "U2") (pin "3") (pinfunction "S2_3") (pintype "passive"))
    )
    (net (code "59") (name "Net-(U3-EN)") (class "Default")
      (node (ref "C1") (pin "2") (pinfunction "2_2") (pintype "passive"))
      (node (ref "C2") (pin "2") (pinfunction "2_2") (pintype "passive"))
      (node (ref "CN1") (pin "MP1") (pinfunction "MP1_MP1") (pintype "passive"))
      (node (ref "R2") (pin "2") (pinfunction "2_2") (pintype "passive"))
      (node (ref "U3") (pin "1") (pinfunction "VIN_1") (pintype "passive"))
      (node (ref "U3") (pin "8") (pinfunction "EN_8") (pintype "passive"))
    )
    (net (code "60") (name "Net-(U3-FB)") (class "Default")
      (node (ref "R12") (pin "1") (pinfunction "1_1") (pintype "passive"))
      (node (ref "R20") (pin "1") (pinfunction "1_1") (pintype "passive"))
      (node (ref "U3") (pin "5") (pinfunction "FB_5") (pintype "passive"))
    )
    (net (code "61") (name "Net-(U3-MODE)") (class "Default")
      (node (ref "C5") (pin "2") (pinfunction "2_2") (pintype "passive"))
      (node (ref "U3") (pin "10") (pinfunction "MODE_10") (pintype "passive"))
    )
    (net (code "62") (name "Net-(U3-PG)") (class "Default")
      (node (ref "R4") (pin "1") (pinfunction "1_1") (pintype "passive"))
      (node (ref "U3") (pin "7") (pinfunction "PG_7") (pintype "passive"))
    )
    (net (code "63") (name "Net-(U3-SS{slash}TR)") (class "Default")
      (node (ref "R11") (pin "1") (pinfunction "1_1") (pintype "passive"))
      (node (ref "R25") (pin "2") (pinfunction "2_2") (pintype "passive"))
      (node (ref "U3") (pin "9") (pinfunction "SS/TR_9") (pintype "passive"))
    )
    (net (code "64") (name "Net-(U3-SW)") (class "Default")
      (node (ref "L1") (pin "1") (pinfunction "1_1") (pintype "passive"))
      (node (ref "U3") (pin "2") (pinfunction "SW_2") (pintype "passive"))
    )
    (net (code "65") (name "Net-(U4--IN)") (class "Default")
      (node (ref "R8") (pin "2") (pinfunction "2_2") (pintype "passive"))
      (node (ref "U4") (pin "3") (pinfunction "-IN_3") (pintype "passive"))
    )
    (net (code "66") (name "Net-(U4-OUT)") (class "Default")
      (node (ref "R13") (pin "2") (pinfunction "2_2") (pintype "passive"))
      (node (ref "R17") (pin "1") (pinfunction "1_1") (pintype "passive"))
      (node (ref "U4") (pin "1") (pinfunction "OUT_1") (pintype "passive"))
    )
    (net (code "67") (name "Net-(U4-V-)") (class "Default")
      (node (ref "R21") (pin "2") (pinfunction "2_2") (pintype "passive"))
      (node (ref "U4") (pin "2") (pinfunction "V-_2") (pintype "passive"))
    )
    (net (code "68") (name "Net-(U5-NC-Pad2)") (class "Default")
      (node (ref "U5") (pin "2") (pinfunction "NC_2") (pintype "passive"))
      (node (ref "U5") (pin "9") (pinfunction "NC_9") (pintype "passive"))
    )
    (net (code "69") (name "Net-(U8-GND)") (class "Default")
      (node (ref "R44") (pin "1") (pinfunction "1_1") (pintype "passive"))
      (node (ref "U8") (pin "2") (pinfunction "GND_2") (pintype "passive"))
      (node (ref "U8") (pin "3") (pinfunction "REF2_3") (pintype "passive"))
      (node (ref "U8") (pin "4") (pinfunction "NC_4") (pintype "passive"))
    )
    (net (code "70") (name "Net-(U8-OUT)") (class "Default")
      (node (ref "R30") (pin "1") (pinfunction "1_1") (pintype "passive"))
      (node (ref "U8") (pin "5") (pinfunction "OUT_5") (pintype "passive"))
    )
    (net (code "71") (name "Net-(U9-BST1)") (class "Default")
      (node (ref "C13") (pin "1") (pinfunction "1_1") (pintype "passive"))
      (node (ref "U9") (pin "23") (pinfunction "BST1_23") (pintype "passive"))
    )
    (net (code "72") (name "Net-(U9-BST2)") (class "Default")
      (node (ref "C14") (pin "1") (pinfunction "1_1") (pintype "passive"))
      (node (ref "U9") (pin "28") (pinfunction "BST2_28") (pintype "passive"))
    )
    (net (code "73") (name "Net-(U9-FB)") (class "Default")
      (node (ref "R48") (pin "2") (pinfunction "2_2") (pintype "passive"))
      (node (ref "R54") (pin "1") (pinfunction "1_1") (pintype "passive"))
      (node (ref "U9") (pin "9") (pinfunction "FB_9") (pintype "passive"))
    )
    (net (code "74") (name "Net-(U9-MPPC)") (class "Default")
      (node (ref "R45") (pin "1") (pinfunction "1_1") (pintype "passive"))
      (node (ref "R45") (pin "2") (pinfunction "2_2") (pintype "passive"))
      (node (ref "R46") (pin "1") (pinfunction "1_1") (pintype "passive"))
      (node (ref "R51") (pin "1") (pinfunction "1_1") (pintype "passive"))
      (node (ref "R53") (pin "1") (pinfunction "1_1") (pintype "passive"))
      (node (ref "U9") (pin "12") (pinfunction "MPPC_12") (pintype "passive"))
    )
    (net (code "75") (name "Net-(U9-PGOOD)") (class "Default")
      (node (ref "R49") (pin "1") (pinfunction "1_1") (pintype "passive"))
      (node (ref "U9") (pin "7") (pinfunction "PGOOD_7") (pintype "passive"))
    )
    (net (code "76") (name "Net-(U9-RT)") (class "Default")
      (node (ref "R52") (pin "1") (pinfunction "1_1") (pintype "passive"))
      (node (ref "U9") (pin "14") (pinfunction "RT_14") (pintype "passive"))
    )
    (net (code "77") (name "Net-(U9-SVcc)") (class "Default")
      (node (ref "C19") (pin "1") (pinfunction "1_1") (pintype "passive"))
      (node (ref "R49") (pin "2") (pinfunction "2_2") (pintype "passive"))
      (node (ref "U9") (pin "13") (pinfunction "Vcc_13") (pintype "passive"))
      (node (ref "U9") (pin "8") (pinfunction "SVcc_8") (pintype "passive"))
    )
    (net (code "78") (name "Net-(U9-VC)") (class "Default")
      (node (ref "R50") (pin "1") (pinfunction "1_1") (pintype "passive"))
      (node (ref "U9") (pin "10") (pinfunction "VC_10") (pintype "passive"))
    )
    (net (code "79") (name "unconnected-(BAT1-Pad4)") (class "Default")
      (node (ref "BAT1") (pin "4") (pinfunction "4_4") (pintype "passive+no_connect"))
    )
    (net (code "80") (name "unconnected-(CN1-Pad1)") (class "Default")
      (node (ref "CN1") (pin "1") (pinfunction "1_1") (pintype "passive"))
    )
    (net (code "81") (name "unconnected-(CN1-Pad2)") (class "Default")
      (node (ref "CN1") (pin "2") (pinfunction "2_2") (pintype "passive"))
    )
    (net (code "82") (name "unconnected-(CN2-Pad1)") (class "Default")
      (node (ref "CN2") (pin "1") (pinfunction "1_1") (pintype "passive"))
    )
    (net (code "83") (name "unconnected-(CN2-Pad2)") (class "Default")
      (node (ref "CN2") (pin "2") (pinfunction "2_2") (pintype "passive"))
    )
    (net (code "84") (name "unconnected-(CN3-Pad1)") (class "Default")
      (node (ref "CN3") (pin "1") (pinfunction "1_1") (pintype "passive"))
    )
    (net (code "85") (name "unconnected-(CN3-Pad2)") (class "Default")
      (node (ref "CN3") (pin "2") (pinfunction "2_2") (pintype "passive"))
    )
    (net (code "86") (name "unconnected-(CN4-Pad1)") (class "Default")
      (node (ref "CN4") (pin "1") (pinfunction "1_1") (pintype "passive"))
    )
    (net (code "87") (name "unconnected-(CN4-Pad2)") (class "Default")
      (node (ref "CN4") (pin "2") (pinfunction "2_2") (pintype "passive"))
    )
    (net (code "88") (name "unconnected-(CN5-Pad2)") (class "Default")
      (node (ref "CN5") (pin "2") (pinfunction "2_2") (pintype "passive"))
    )
    (net (code "89") (name "unconnected-(CN5-PadMP1)") (class "Default")
      (node (ref "CN5") (pin "MP1") (pinfunction "MP1_MP1") (pintype "passive"))
    )
    (net (code "90") (name "unconnected-(CN5-PadMP2)") (class "Default")
      (node (ref "CN5") (pin "MP2") (pinfunction "MP2_MP2") (pintype "passive"))
    )
    (net (code "91") (name "unconnected-(CN6-PadMP1)") (class "Default")
      (node (ref "CN6") (pin "MP1") (pinfunction "MP1_MP1") (pintype "passive"))
    )
    (net (code "92") (name "unconnected-(CN6-PadMP2)") (class "Default")
      (node (ref "CN6") (pin "MP2") (pinfunction "MP2_MP2") (pintype "passive"))
    )
    (net (code "93") (name "unconnected-(CN7-Pad1)") (class "Default")
      (node (ref "CN7") (pin "1") (pinfunction "1_1") (pintype "passive"))
    )
    (net (code "94") (name "unconnected-(CN7-Pad2)") (class "Default")
      (node (ref "CN7") (pin "2") (pinfunction "2_2") (pintype "passive"))
    )
    (net (code "95") (name "unconnected-(CN8-PadMP1)") (class "Default")
      (node (ref "CN8") (pin "MP1") (pinfunction "MP1_MP1") (pintype "passive"))
    )
    (net (code "96") (name "unconnected-(CN8-PadMP2)") (class "Default")
      (node (ref "CN8") (pin "MP2") (pinfunction "MP2_MP2") (pintype "passive"))
    )
    (net (code "97") (name "unconnected-(D1-K-Pad2)") (class "Default")
      (node (ref "D1") (pin "2") (pinfunction "K_2") (pintype "passive"))
    )
    (net (code "98") (name "unconnected-(D5-K-Pad2)") (class "Default")
      (node (ref "D5") (pin "2") (pinfunction "K_2") (pintype "passive"))
    )
    (net (code "99") (name "unconnected-(D7-K-Pad2)") (class "Default")
      (node (ref "D7") (pin "2") (pinfunction "K_2") (pintype "passive"))
    )
    (net (code "100") (name "unconnected-(J2-Pad2)") (class "Default")
      (node (ref "J2") (pin "2") (pinfunction "2_2") (pintype "passive"))
    )
    (net (code "101") (name "unconnected-(J_Antenna1-Pad1)") (class "Default")
      (node (ref "J_Antenna1") (pin "1") (pinfunction "1_1") (pintype "passive+no_connect"))
    )
    (net (code "102") (name "unconnected-(J_Antenna1-Pad2)") (class "Default")
      (node (ref "J_Antenna1") (pin "2") (pinfunction "2_2") (pintype "passive+no_connect"))
    )
    (net (code "103") (name "unconnected-(J_Antenna1-Pad3)") (class "Default")
      (node (ref "J_Antenna1") (pin "3") (pinfunction "3_3") (pintype "passive+no_connect"))
    )
    (net (code "104") (name "unconnected-(L2-Pad1)") (class "Default")
      (node (ref "L2") (pin "1") (pinfunction "1_1") (pintype "passive"))
    )
    (net (code "105") (name "unconnected-(R1-E1-Pad3)") (class "Default")
      (node (ref "R1") (pin "3") (pinfunction "E1_3") (pintype "passive"))
    )
    (net (code "106") (name "unconnected-(R1-E2-Pad4)") (class "Default")
      (node (ref "R1") (pin "4") (pinfunction "E2_4") (pintype "passive"))
    )
    (net (code "107") (name "unconnected-(R5-E1-Pad3)") (class "Default")
      (node (ref "R5") (pin "3") (pinfunction "E1_3") (pintype "passive"))
    )
    (net (code "108") (name "unconnected-(R5-E2-Pad4)") (class "Default")
      (node (ref "R5") (pin "4") (pinfunction "E2_4") (pintype "passive"))
    )
    (net (code "109") (name "unconnected-(R13-Pad1)") (class "Default")
      (node (ref "R13") (pin "1") (pinfunction "1_1") (pintype "passive"))
    )
    (net (code "110") (name "unconnected-(R16-Pad2)") (class "Default")
      (node (ref "R16") (pin "2") (pinfunction "2_2") (pintype "passive"))
    )
    (net (code "111") (name "unconnected-(R18-Pad2)") (class "Default")
      (node (ref "R18") (pin "2") (pinfunction "2_2") (pintype "passive"))
    )
    (net (code "112") (name "unconnected-(R19-Pad2)") (class "Default")
      (node (ref "R19") (pin "2") (pinfunction "2_2") (pintype "passive"))
    )
    (net (code "113") (name "unconnected-(R27-Pad2)") (class "Default")
      (node (ref "R27") (pin "2") (pinfunction "2_2") (pintype "passive"))
    )
    (net (code "114") (name "unconnected-(R28-Pad2)") (class "Default")
      (node (ref "R28") (pin "2") (pinfunction "2_2") (pintype "passive"))
    )
    (net (code "115") (name "unconnected-(R30-Pad2)") (class "Default")
      (node (ref "R30") (pin "2") (pinfunction "2_2") (pintype "passive"))
    )
    (net (code "116") (name "unconnected-(R32-E1-Pad3)") (class "Default")
      (node (ref "R32") (pin "3") (pinfunction "E1_3") (pintype "passive"))
    )
    (net (code "117") (name "unconnected-(R32-E2-Pad4)") (class "Default")
      (node (ref "R32") (pin "4") (pinfunction "E2_4") (pintype "passive"))
    )
    (net (code "118") (name "unconnected-(R33-E1-Pad3)") (class "Default")
      (node (ref "R33") (pin "3") (pinfunction "E1_3") (pintype "passive"))
    )
    (net (code "119") (name "unconnected-(R33-E2-Pad4)") (class "Default")
      (node (ref "R33") (pin "4") (pinfunction "E2_4") (pintype "passive"))
    )
    (net (code "120") (name "unconnected-(R35-Pad1)") (class "Default")
      (node (ref "R35") (pin "1") (pinfunction "1_1") (pintype "passive"))
    )
    (net (code "121") (name "unconnected-(R38-Pad2)") (class "Default")
      (node (ref "R38") (pin "2") (pinfunction "2_2") (pintype "passive+no_connect"))
    )
    (net (code "122") (name "unconnected-(R39-Pad2)") (class "Default")
      (node (ref "R39") (pin "2") (pinfunction "2_2") (pintype "passive+no_connect"))
    )
    (net (code "123") (name "unconnected-(R40-Pad2)") (class "Default")
      (node (ref "R40") (pin "2") (pinfunction "2_2") (pintype "passive+no_connect"))
    )
    (net (code "124") (name "unconnected-(R44-Pad2)") (class "Default")
      (node (ref "R44") (pin "2") (pinfunction "2_2") (pintype "passive"))
    )
    (net (code "125") (name "unconnected-(U6-EN-Pad8)") (class "Default")
      (node (ref "U6") (pin "8") (pinfunction "EN_8") (pintype "input"))
    )
    (net (code "126") (name "unconnected-(U6-FB2-Pad4)") (class "Default")
      (node (ref "U6") (pin "4") (pinfunction "FB2_4") (pintype "input"))
    )
    (net (code "127") (name "unconnected-(U6-GND-Pad3)") (class "Default")
      (node (ref "U6") (pin "3") (pinfunction "GND_3") (pintype "power_in"))
    )
    (net (code "128") (name "unconnected-(U6-MODE-Pad10)") (class "Default")
      (node (ref "U6") (pin "10") (pinfunction "MODE_10") (pintype "input"))
    )
    (net (code "129") (name "unconnected-(U6-PG-Pad7)") (class "Default")
      (node (ref "U6") (pin "7") (pinfunction "PG_7") (pintype "open_collector"))
    )
    (net (code "130") (name "unconnected-(U6-SS_TR-Pad9)") (class "Default")
      (node (ref "U6") (pin "9") (pinfunction "SS_TR_9") (pintype "input"))
    )
    (net (code "131") (name "unconnected-(U6-SW-Pad2)") (class "Default")
      (node (ref "U6") (pin "2") (pinfunction "SW_2") (pintype "power_in"))
    )
    (net (code "132") (name "unconnected-(U6-VIN-Pad1)") (class "Default")
      (node (ref "U6") (pin "1") (pinfunction "VIN_1") (pintype "power_in"))
    )
    (net (code "133") (name "unconnected-(U6-VOS-Pad6)") (class "Default")
      (node (ref "U6") (pin "6") (pinfunction "VOS_6") (pintype "input"))
    )
    (net (code "134") (name "unconnected-(U6-VSEL-Pad11)") (class "Default")
      (node (ref "U6") (pin "11") (pinfunction "VSEL_11") (pintype "input"))
    )
    (net (code "135") (name "unconnected-(U7-A0-Pad13)") (class "Default")
      (node (ref "U7") (pin "13") (pinfunction "A0_13") (pintype "passive+no_connect"))
    )
    (net (code "136") (name "unconnected-(U7-A3-Pad12)") (class "Default")
      (node (ref "U7") (pin "12") (pinfunction "A3_12") (pintype "passive+no_connect"))
    )
    (net (code "137") (name "unconnected-(U10-BAT-Pad5)") (class "Default")
      (node (ref "U10") (pin "5") (pinfunction "BAT_5") (pintype "power_in"))
    )
    (net (code "138") (name "unconnected-(U10-EP-Pad9)") (class "Default")
      (node (ref "U10") (pin "9") (pinfunction "EP_9") (pintype "passive"))
    )
    (net (code "139") (name "unconnected-(U10-FB-Pad8)") (class "Default")
      (node (ref "U10") (pin "8") (pinfunction "FB_8") (pintype "input"))
    )
    (net (code "140") (name "unconnected-(U10-GND-Pad3)") (class "Default")
      (node (ref "U10") (pin "3") (pinfunction "GND_3") (pintype "power_in"))
    )
    (net (code "141") (name "unconnected-(U10-ISET-Pad2)") (class "Default")
      (node (ref "U10") (pin "2") (pinfunction "ISET_2") (pintype "input"))
    )
    (net (code "142") (name "unconnected-(U10-TEMP-Pad1)") (class "Default")
      (node (ref "U10") (pin "1") (pinfunction "TEMP_1") (pintype "input"))
    )
    (net (code "143") (name "unconnected-(U10-VIN-Pad4)") (class "Default")
      (node (ref "U10") (pin "4") (pinfunction "VIN_4") (pintype "power_in"))
    )
    (net (code "144") (name "unconnected-(U10-~{CHRG}-Pad7)") (class "Default")
      (node (ref "U10") (pin "7") (pinfunction "~{CHRG}_7") (pintype "tri_state"))
    )
    (net (code "145") (name "unconnected-(U10-~{DONE}-Pad6)") (class "Default")
      (node (ref "U10") (pin "6") (pinfunction "~{DONE}_6") (pintype "tri_state"))
    )
    (net (code "146") (name "unconnected-(U11-A5-Pad5)") (class "Default")
      (node (ref "U11") (pin "5") (pinfunction "A5_5") (pintype "passive+no_connect"))
    )
  )
)
